# REV1.net
KiCad netlist of a schematic drawn in EAGLE
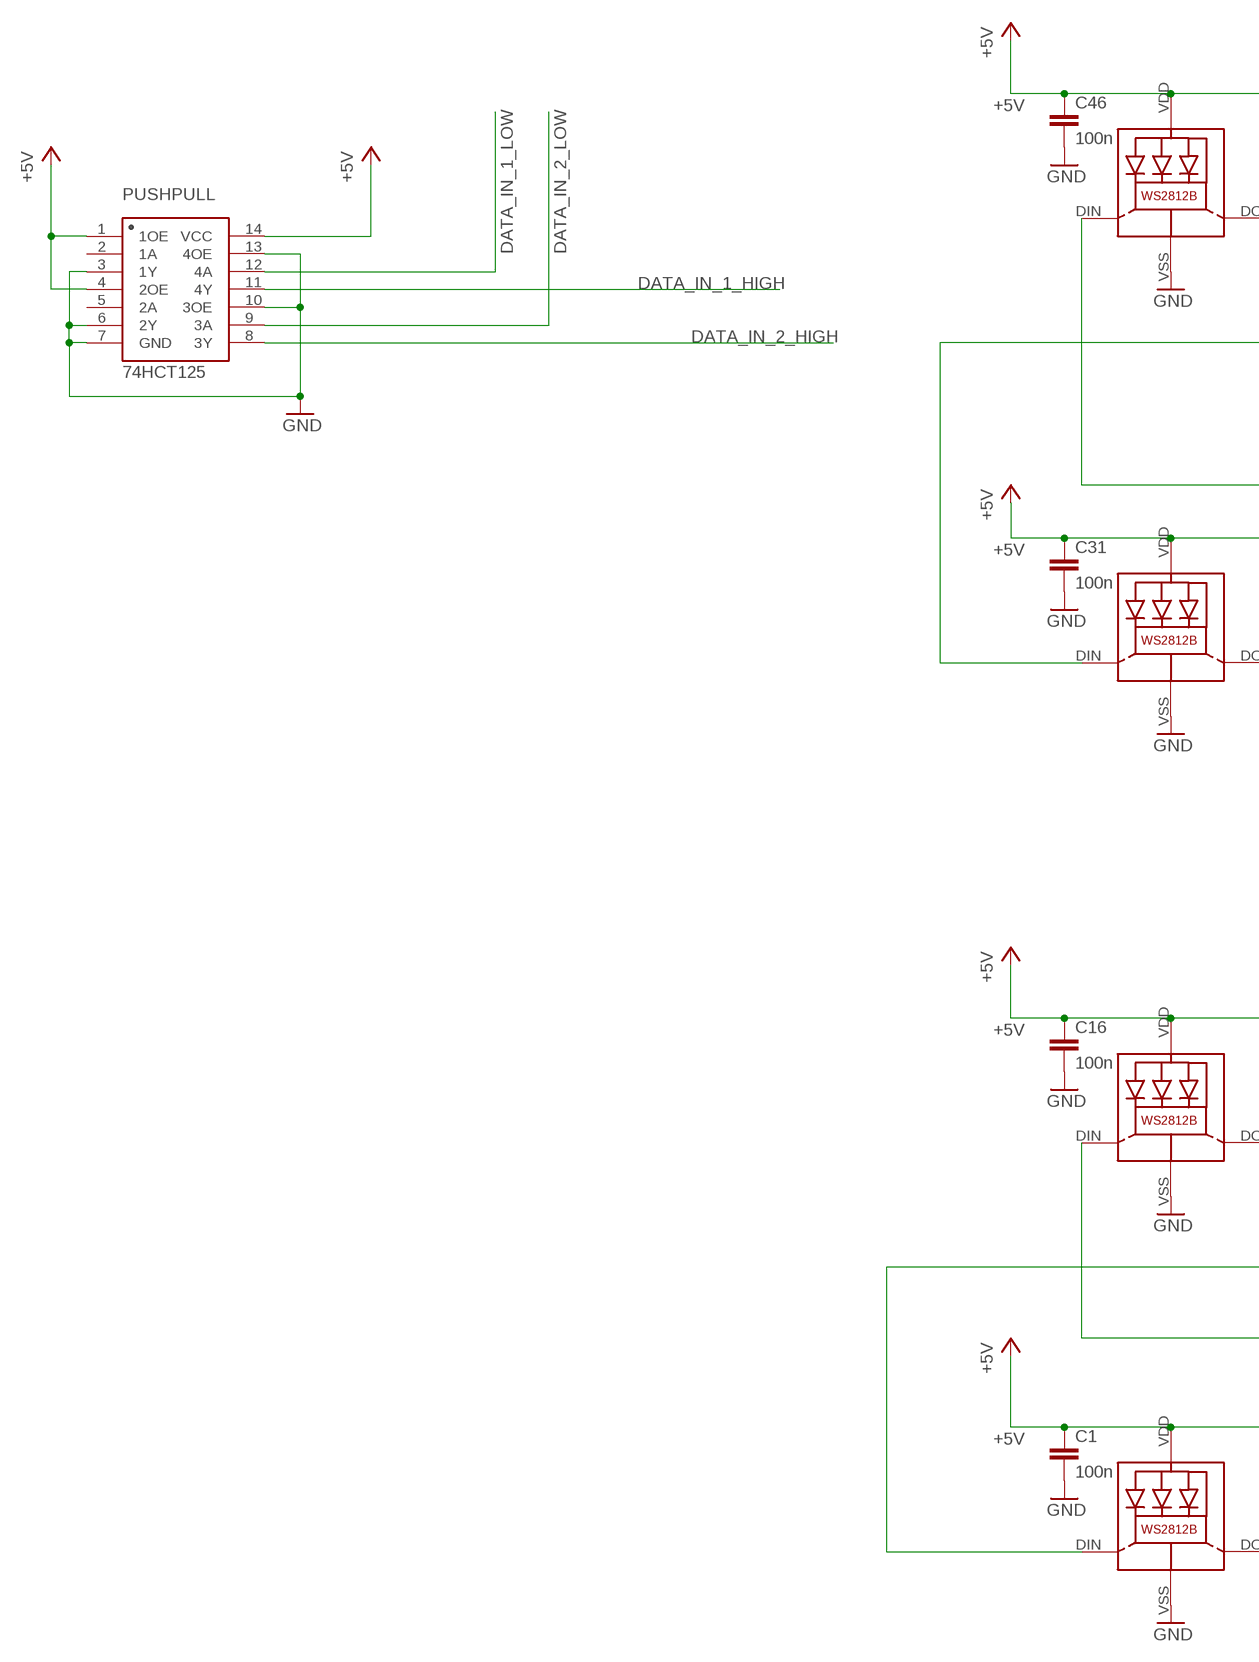
[diagram p0: schematic, sheet 1, part 1 of 2]
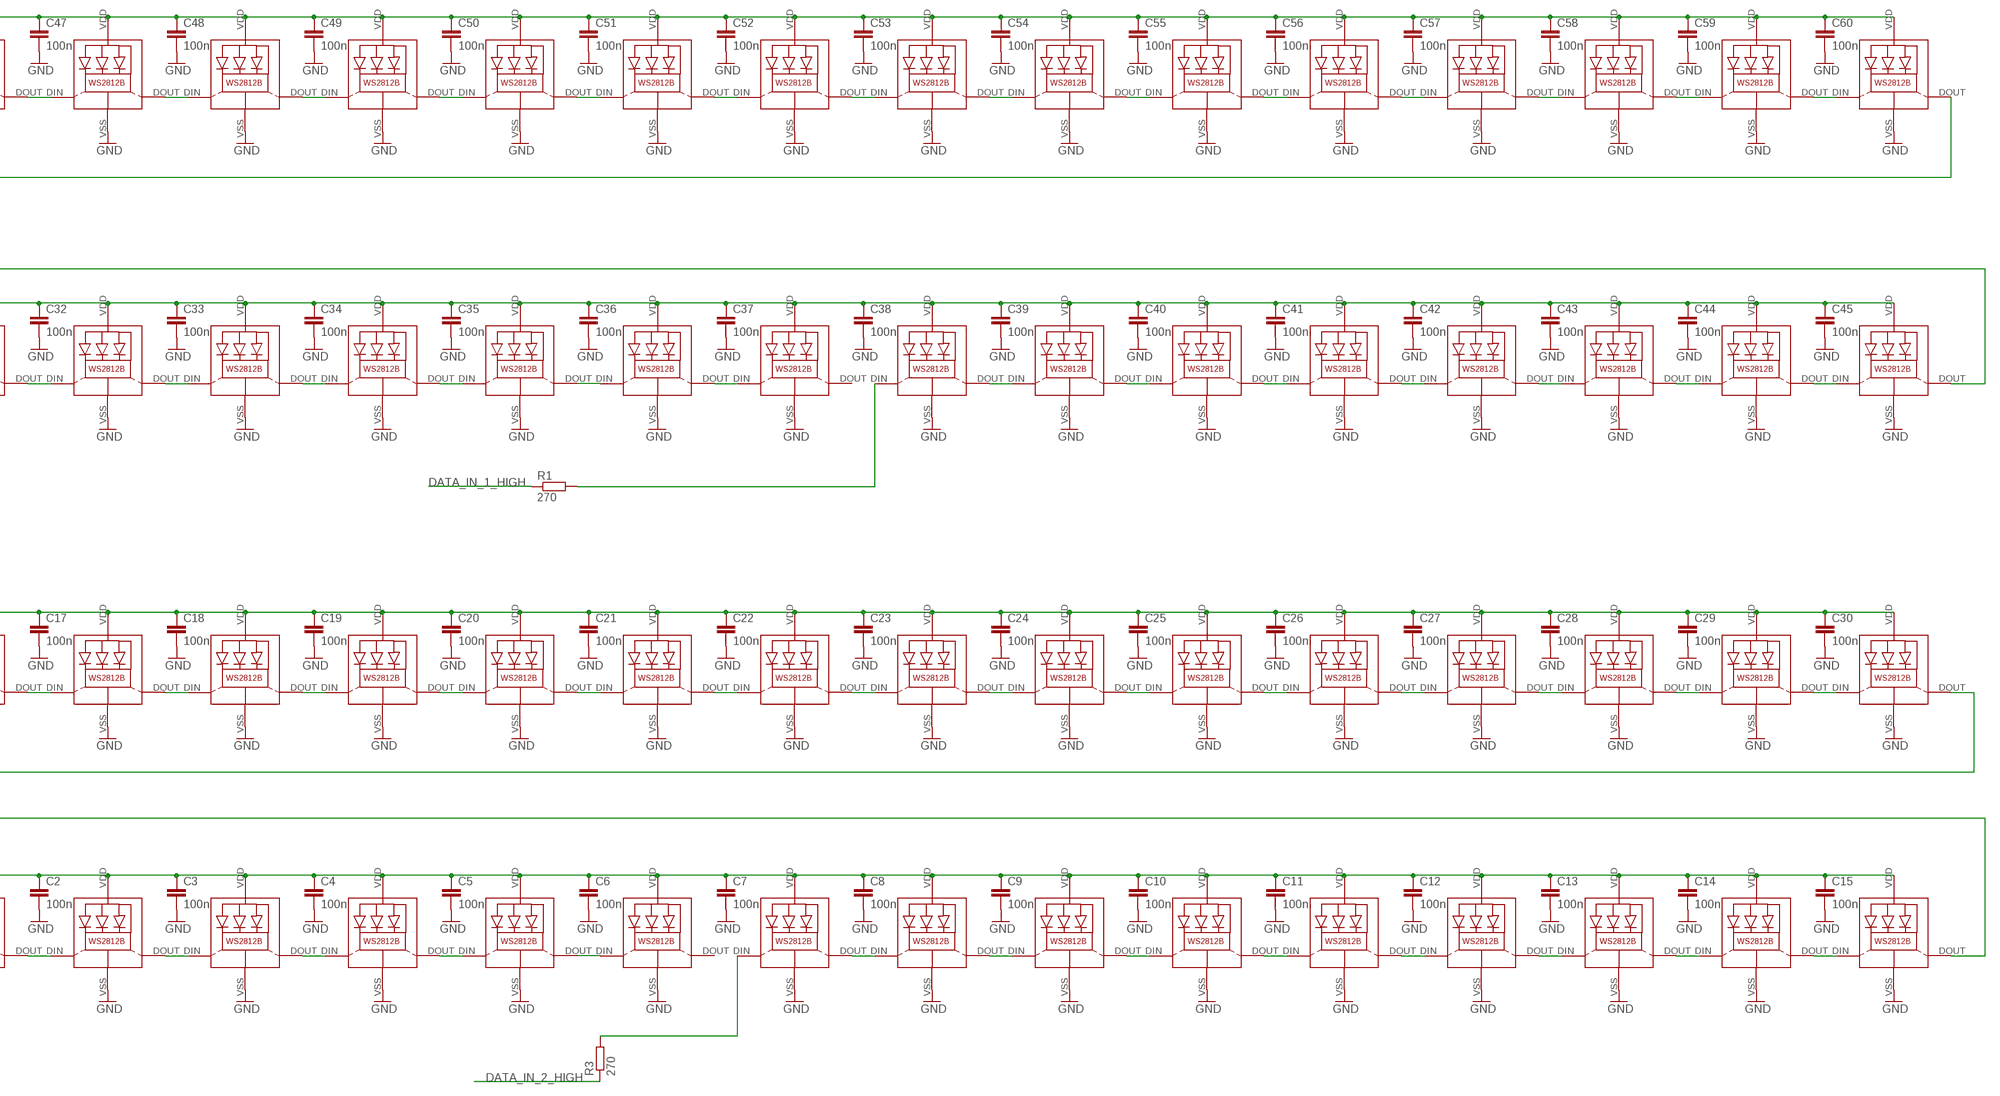
[diagram p1: schematic, sheet 1, part 2 of 2]
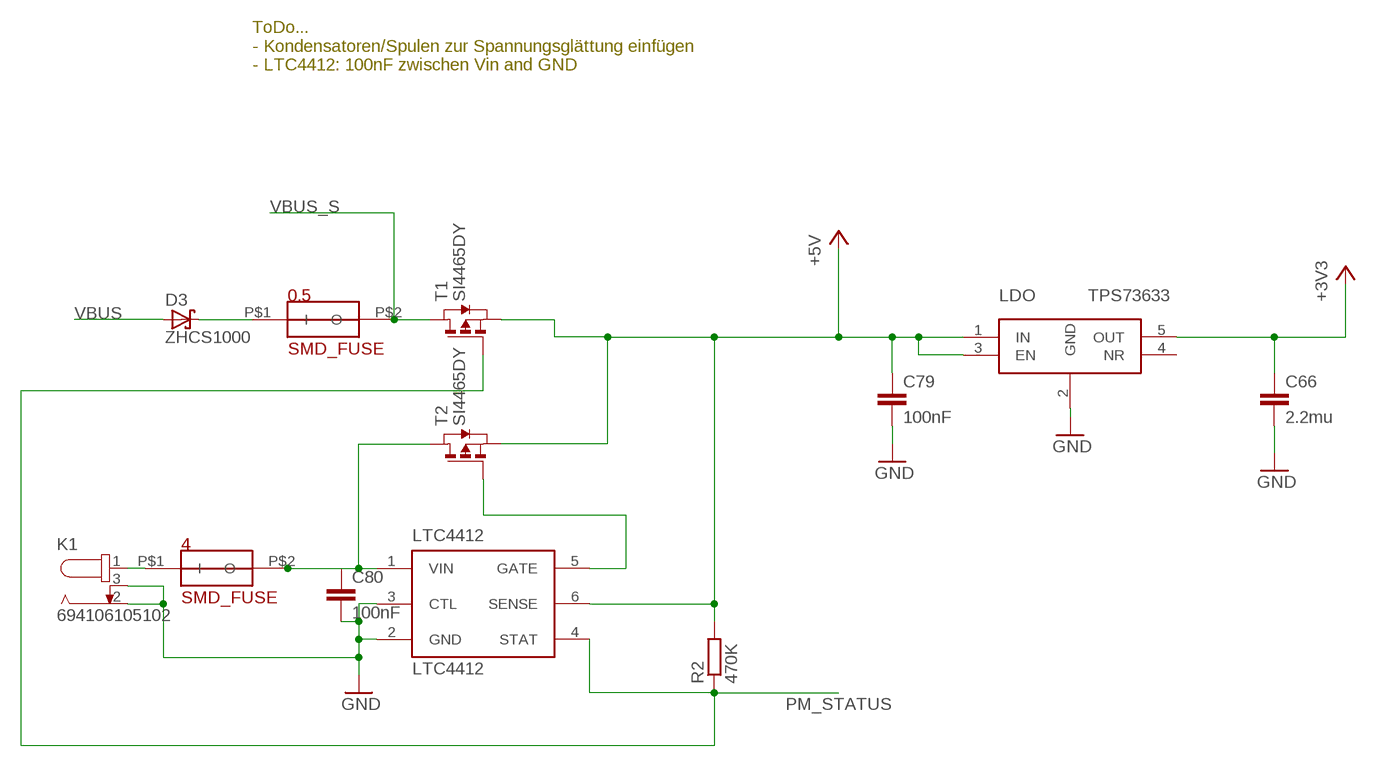
[diagram p2: schematic, sheet 2]
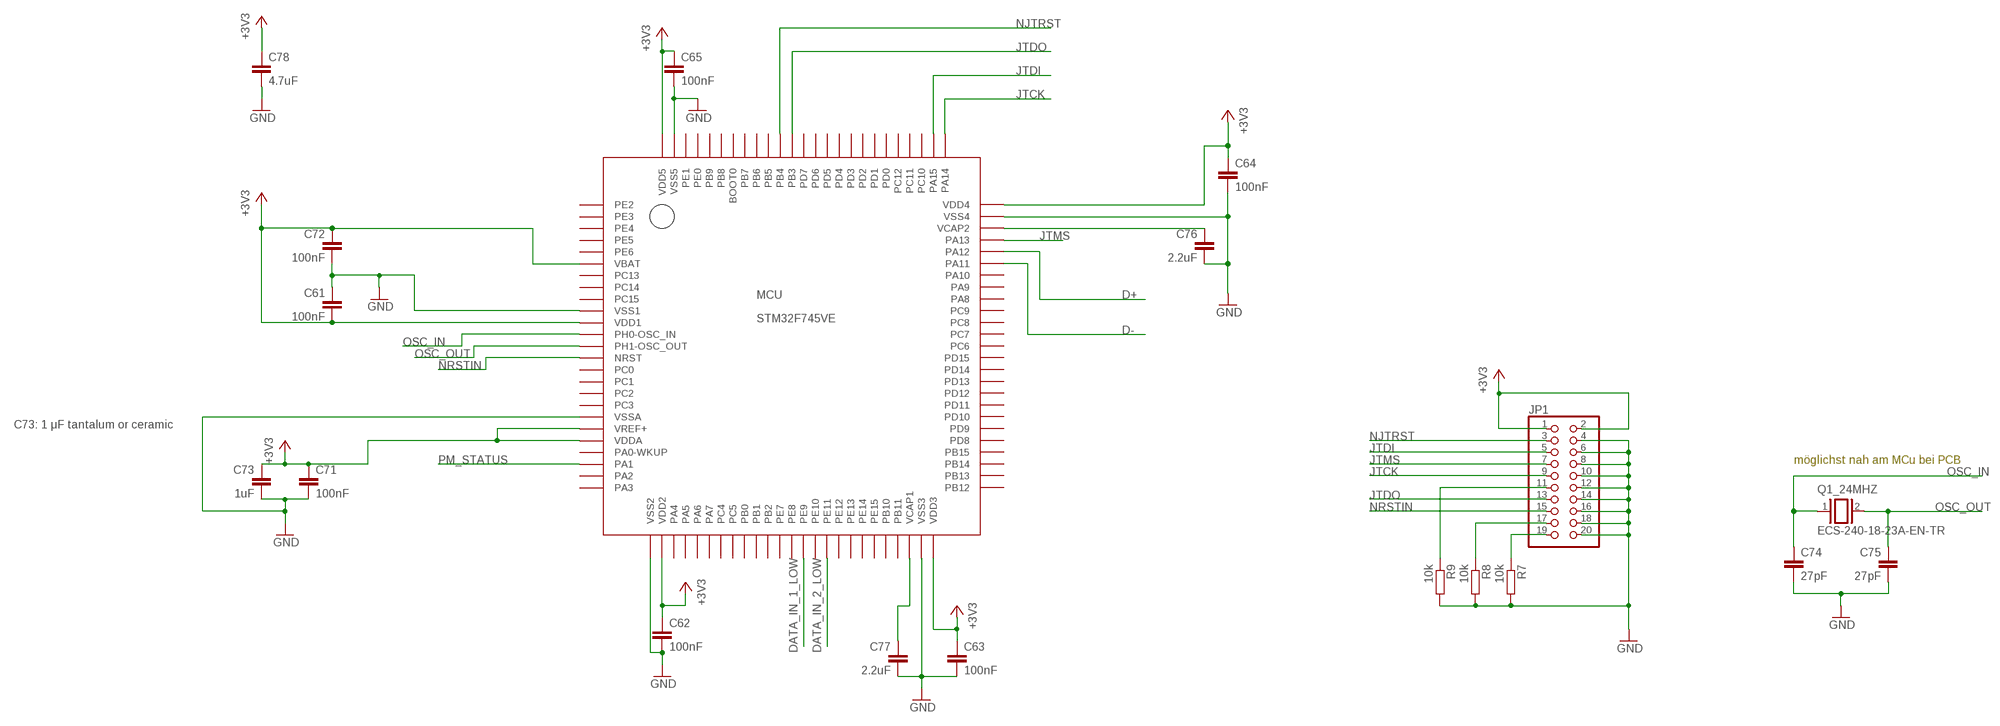
[diagram p3: schematic, sheet 3]
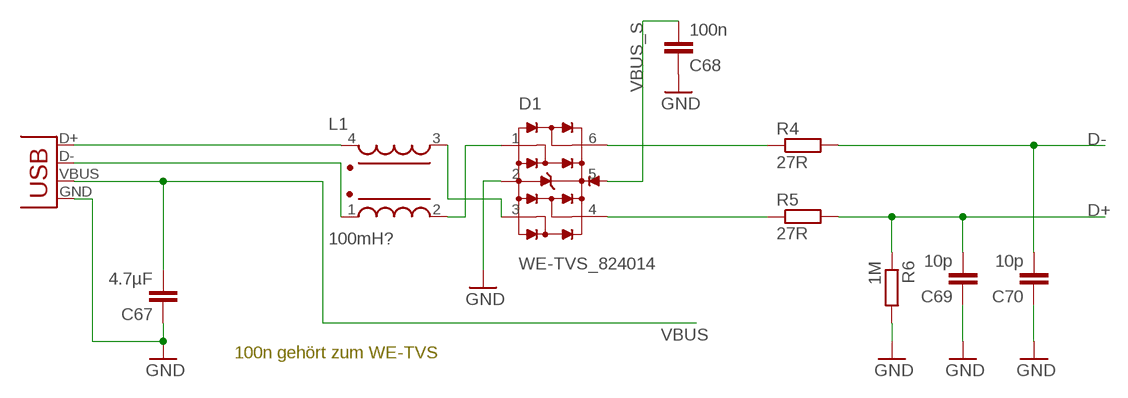
[diagram p4: schematic, sheet 4]

(export (version "E")
  (design (tool "Eeschema 10.0.6"))
  (components
    (comp (ref "C1")
      (value "100n")
      (footprint "eagle-import:C0603")
      (libsource (lib "eagle-import") (part "C-EUC0603"))
    )
    (comp (ref "C2")
      (value "100n")
      (footprint "eagle-import:C0603")
      (libsource (lib "eagle-import") (part "C-EUC0603"))
    )
    (comp (ref "C3")
      (value "100n")
      (footprint "eagle-import:C0603")
      (libsource (lib "eagle-import") (part "C-EUC0603"))
    )
    (comp (ref "C4")
      (value "100n")
      (footprint "eagle-import:C0603")
      (libsource (lib "eagle-import") (part "C-EUC0603"))
    )
    (comp (ref "C5")
      (value "100n")
      (footprint "eagle-import:C0603")
      (libsource (lib "eagle-import") (part "C-EUC0603"))
    )
    (comp (ref "C6")
      (value "100n")
      (footprint "eagle-import:C0603")
      (libsource (lib "eagle-import") (part "C-EUC0603"))
    )
    (comp (ref "C7")
      (value "100n")
      (footprint "eagle-import:C0603")
      (libsource (lib "eagle-import") (part "C-EUC0603"))
    )
    (comp (ref "C8")
      (value "100n")
      (footprint "eagle-import:C0603")
      (libsource (lib "eagle-import") (part "C-EUC0603"))
    )
    (comp (ref "C9")
      (value "100n")
      (footprint "eagle-import:C0603")
      (libsource (lib "eagle-import") (part "C-EUC0603"))
    )
    (comp (ref "C10")
      (value "100n")
      (footprint "eagle-import:C0603")
      (libsource (lib "eagle-import") (part "C-EUC0603"))
    )
    (comp (ref "C11")
      (value "100n")
      (footprint "eagle-import:C0603")
      (libsource (lib "eagle-import") (part "C-EUC0603"))
    )
    (comp (ref "C12")
      (value "100n")
      (footprint "eagle-import:C0603")
      (libsource (lib "eagle-import") (part "C-EUC0603"))
    )
    (comp (ref "C13")
      (value "100n")
      (footprint "eagle-import:C0603")
      (libsource (lib "eagle-import") (part "C-EUC0603"))
    )
    (comp (ref "C14")
      (value "100n")
      (footprint "eagle-import:C0603")
      (libsource (lib "eagle-import") (part "C-EUC0603"))
    )
    (comp (ref "C15")
      (value "100n")
      (footprint "eagle-import:C0603")
      (libsource (lib "eagle-import") (part "C-EUC0603"))
    )
    (comp (ref "C16")
      (value "100n")
      (footprint "eagle-import:C0603")
      (libsource (lib "eagle-import") (part "C-EUC0603"))
    )
    (comp (ref "C17")
      (value "100n")
      (footprint "eagle-import:C0603")
      (libsource (lib "eagle-import") (part "C-EUC0603"))
    )
    (comp (ref "C18")
      (value "100n")
      (footprint "eagle-import:C0603")
      (libsource (lib "eagle-import") (part "C-EUC0603"))
    )
    (comp (ref "C19")
      (value "100n")
      (footprint "eagle-import:C0603")
      (libsource (lib "eagle-import") (part "C-EUC0603"))
    )
    (comp (ref "C20")
      (value "100n")
      (footprint "eagle-import:C0603")
      (libsource (lib "eagle-import") (part "C-EUC0603"))
    )
    (comp (ref "C21")
      (value "100n")
      (footprint "eagle-import:C0603")
      (libsource (lib "eagle-import") (part "C-EUC0603"))
    )
    (comp (ref "C22")
      (value "100n")
      (footprint "eagle-import:C0603")
      (libsource (lib "eagle-import") (part "C-EUC0603"))
    )
    (comp (ref "C23")
      (value "100n")
      (footprint "eagle-import:C0603")
      (libsource (lib "eagle-import") (part "C-EUC0603"))
    )
    (comp (ref "C24")
      (value "100n")
      (footprint "eagle-import:C0603")
      (libsource (lib "eagle-import") (part "C-EUC0603"))
    )
    (comp (ref "C25")
      (value "100n")
      (footprint "eagle-import:C0603")
      (libsource (lib "eagle-import") (part "C-EUC0603"))
    )
    (comp (ref "C26")
      (value "100n")
      (footprint "eagle-import:C0603")
      (libsource (lib "eagle-import") (part "C-EUC0603"))
    )
    (comp (ref "C27")
      (value "100n")
      (footprint "eagle-import:C0603")
      (libsource (lib "eagle-import") (part "C-EUC0603"))
    )
    (comp (ref "C28")
      (value "100n")
      (footprint "eagle-import:C0603")
      (libsource (lib "eagle-import") (part "C-EUC0603"))
    )
    (comp (ref "C29")
      (value "100n")
      (footprint "eagle-import:C0603")
      (libsource (lib "eagle-import") (part "C-EUC0603"))
    )
    (comp (ref "C30")
      (value "100n")
      (footprint "eagle-import:C0603")
      (libsource (lib "eagle-import") (part "C-EUC0603"))
    )
    (comp (ref "C31")
      (value "100n")
      (footprint "eagle-import:C0603")
      (libsource (lib "eagle-import") (part "C-EUC0603"))
    )
    (comp (ref "C32")
      (value "100n")
      (footprint "eagle-import:C0603")
      (libsource (lib "eagle-import") (part "C-EUC0603"))
    )
    (comp (ref "C33")
      (value "100n")
      (footprint "eagle-import:C0603")
      (libsource (lib "eagle-import") (part "C-EUC0603"))
    )
    (comp (ref "C34")
      (value "100n")
      (footprint "eagle-import:C0603")
      (libsource (lib "eagle-import") (part "C-EUC0603"))
    )
    (comp (ref "C35")
      (value "100n")
      (footprint "eagle-import:C0603")
      (libsource (lib "eagle-import") (part "C-EUC0603"))
    )
    (comp (ref "C36")
      (value "100n")
      (footprint "eagle-import:C0603")
      (libsource (lib "eagle-import") (part "C-EUC0603"))
    )
    (comp (ref "C37")
      (value "100n")
      (footprint "eagle-import:C0603")
      (libsource (lib "eagle-import") (part "C-EUC0603"))
    )
    (comp (ref "C38")
      (value "100n")
      (footprint "eagle-import:C0603")
      (libsource (lib "eagle-import") (part "C-EUC0603"))
    )
    (comp (ref "C39")
      (value "100n")
      (footprint "eagle-import:C0603")
      (libsource (lib "eagle-import") (part "C-EUC0603"))
    )
    (comp (ref "C40")
      (value "100n")
      (footprint "eagle-import:C0603")
      (libsource (lib "eagle-import") (part "C-EUC0603"))
    )
    (comp (ref "C41")
      (value "100n")
      (footprint "eagle-import:C0603")
      (libsource (lib "eagle-import") (part "C-EUC0603"))
    )
    (comp (ref "C42")
      (value "100n")
      (footprint "eagle-import:C0603")
      (libsource (lib "eagle-import") (part "C-EUC0603"))
    )
    (comp (ref "C43")
      (value "100n")
      (footprint "eagle-import:C0603")
      (libsource (lib "eagle-import") (part "C-EUC0603"))
    )
    (comp (ref "C44")
      (value "100n")
      (footprint "eagle-import:C0603")
      (libsource (lib "eagle-import") (part "C-EUC0603"))
    )
    (comp (ref "C45")
      (value "100n")
      (footprint "eagle-import:C0603")
      (libsource (lib "eagle-import") (part "C-EUC0603"))
    )
    (comp (ref "C46")
      (value "100n")
      (footprint "eagle-import:C0603")
      (libsource (lib "eagle-import") (part "C-EUC0603"))
    )
    (comp (ref "C47")
      (value "100n")
      (footprint "eagle-import:C0603")
      (libsource (lib "eagle-import") (part "C-EUC0603"))
    )
    (comp (ref "C48")
      (value "100n")
      (footprint "eagle-import:C0603")
      (libsource (lib "eagle-import") (part "C-EUC0603"))
    )
    (comp (ref "C49")
      (value "100n")
      (footprint "eagle-import:C0603")
      (libsource (lib "eagle-import") (part "C-EUC0603"))
    )
    (comp (ref "C50")
      (value "100n")
      (footprint "eagle-import:C0603")
      (libsource (lib "eagle-import") (part "C-EUC0603"))
    )
    (comp (ref "C51")
      (value "100n")
      (footprint "eagle-import:C0603")
      (libsource (lib "eagle-import") (part "C-EUC0603"))
    )
    (comp (ref "C52")
      (value "100n")
      (footprint "eagle-import:C0603")
      (libsource (lib "eagle-import") (part "C-EUC0603"))
    )
    (comp (ref "C53")
      (value "100n")
      (footprint "eagle-import:C0603")
      (libsource (lib "eagle-import") (part "C-EUC0603"))
    )
    (comp (ref "C54")
      (value "100n")
      (footprint "eagle-import:C0603")
      (libsource (lib "eagle-import") (part "C-EUC0603"))
    )
    (comp (ref "C55")
      (value "100n")
      (footprint "eagle-import:C0603")
      (libsource (lib "eagle-import") (part "C-EUC0603"))
    )
    (comp (ref "C56")
      (value "100n")
      (footprint "eagle-import:C0603")
      (libsource (lib "eagle-import") (part "C-EUC0603"))
    )
    (comp (ref "C57")
      (value "100n")
      (footprint "eagle-import:C0603")
      (libsource (lib "eagle-import") (part "C-EUC0603"))
    )
    (comp (ref "C58")
      (value "100n")
      (footprint "eagle-import:C0603")
      (libsource (lib "eagle-import") (part "C-EUC0603"))
    )
    (comp (ref "C59")
      (value "100n")
      (footprint "eagle-import:C0603")
      (libsource (lib "eagle-import") (part "C-EUC0603"))
    )
    (comp (ref "C60")
      (value "100n")
      (footprint "eagle-import:C0603")
      (libsource (lib "eagle-import") (part "C-EUC0603"))
    )
    (comp (ref "LED1")
      (value "WS2812B")
      (footprint "eagle-import:WS2812B")
      (libsource (lib "eagle-import") (part "WS2812B"))
    )
    (comp (ref "LED2")
      (value "WS2812B")
      (footprint "eagle-import:WS2812B")
      (libsource (lib "eagle-import") (part "WS2812B"))
    )
    (comp (ref "LED3")
      (value "WS2812B")
      (footprint "eagle-import:WS2812B")
      (libsource (lib "eagle-import") (part "WS2812B"))
    )
    (comp (ref "LED4")
      (value "WS2812B")
      (footprint "eagle-import:WS2812B")
      (libsource (lib "eagle-import") (part "WS2812B"))
    )
    (comp (ref "LED5")
      (value "WS2812B")
      (footprint "eagle-import:WS2812B")
      (libsource (lib "eagle-import") (part "WS2812B"))
    )
    (comp (ref "LED6")
      (value "WS2812B")
      (footprint "eagle-import:WS2812B")
      (libsource (lib "eagle-import") (part "WS2812B"))
    )
    (comp (ref "LED7")
      (value "WS2812B")
      (footprint "eagle-import:WS2812B")
      (libsource (lib "eagle-import") (part "WS2812B"))
    )
    (comp (ref "LED8")
      (value "WS2812B")
      (footprint "eagle-import:WS2812B")
      (libsource (lib "eagle-import") (part "WS2812B"))
    )
    (comp (ref "LED9")
      (value "WS2812B")
      (footprint "eagle-import:WS2812B")
      (libsource (lib "eagle-import") (part "WS2812B"))
    )
    (comp (ref "LED10")
      (value "WS2812B")
      (footprint "eagle-import:WS2812B")
      (libsource (lib "eagle-import") (part "WS2812B"))
    )
    (comp (ref "LED11")
      (value "WS2812B")
      (footprint "eagle-import:WS2812B")
      (libsource (lib "eagle-import") (part "WS2812B"))
    )
    (comp (ref "LED12")
      (value "WS2812B")
      (footprint "eagle-import:WS2812B")
      (libsource (lib "eagle-import") (part "WS2812B"))
    )
    (comp (ref "LED13")
      (value "WS2812B")
      (footprint "eagle-import:WS2812B")
      (libsource (lib "eagle-import") (part "WS2812B"))
    )
    (comp (ref "LED14")
      (value "WS2812B")
      (footprint "eagle-import:WS2812B")
      (libsource (lib "eagle-import") (part "WS2812B"))
    )
    (comp (ref "LED15")
      (value "WS2812B")
      (footprint "eagle-import:WS2812B")
      (libsource (lib "eagle-import") (part "WS2812B"))
    )
    (comp (ref "LED16")
      (value "WS2812B")
      (footprint "eagle-import:WS2812B")
      (libsource (lib "eagle-import") (part "WS2812B"))
    )
    (comp (ref "LED17")
      (value "WS2812B")
      (footprint "eagle-import:WS2812B")
      (libsource (lib "eagle-import") (part "WS2812B"))
    )
    (comp (ref "LED18")
      (value "WS2812B")
      (footprint "eagle-import:WS2812B")
      (libsource (lib "eagle-import") (part "WS2812B"))
    )
    (comp (ref "LED19")
      (value "WS2812B")
      (footprint "eagle-import:WS2812B")
      (libsource (lib "eagle-import") (part "WS2812B"))
    )
    (comp (ref "LED20")
      (value "WS2812B")
      (footprint "eagle-import:WS2812B")
      (libsource (lib "eagle-import") (part "WS2812B"))
    )
    (comp (ref "LED21")
      (value "WS2812B")
      (footprint "eagle-import:WS2812B")
      (libsource (lib "eagle-import") (part "WS2812B"))
    )
    (comp (ref "LED22")
      (value "WS2812B")
      (footprint "eagle-import:WS2812B")
      (libsource (lib "eagle-import") (part "WS2812B"))
    )
    (comp (ref "LED23")
      (value "WS2812B")
      (footprint "eagle-import:WS2812B")
      (libsource (lib "eagle-import") (part "WS2812B"))
    )
    (comp (ref "LED24")
      (value "WS2812B")
      (footprint "eagle-import:WS2812B")
      (libsource (lib "eagle-import") (part "WS2812B"))
    )
    (comp (ref "LED25")
      (value "WS2812B")
      (footprint "eagle-import:WS2812B")
      (libsource (lib "eagle-import") (part "WS2812B"))
    )
    (comp (ref "LED26")
      (value "WS2812B")
      (footprint "eagle-import:WS2812B")
      (libsource (lib "eagle-import") (part "WS2812B"))
    )
    (comp (ref "LED27")
      (value "WS2812B")
      (footprint "eagle-import:WS2812B")
      (libsource (lib "eagle-import") (part "WS2812B"))
    )
    (comp (ref "LED28")
      (value "WS2812B")
      (footprint "eagle-import:WS2812B")
      (libsource (lib "eagle-import") (part "WS2812B"))
    )
    (comp (ref "LED29")
      (value "WS2812B")
      (footprint "eagle-import:WS2812B")
      (libsource (lib "eagle-import") (part "WS2812B"))
    )
    (comp (ref "LED30")
      (value "WS2812B")
      (footprint "eagle-import:WS2812B")
      (libsource (lib "eagle-import") (part "WS2812B"))
    )
    (comp (ref "LED31")
      (value "WS2812B")
      (footprint "eagle-import:WS2812B")
      (libsource (lib "eagle-import") (part "WS2812B"))
    )
    (comp (ref "LED32")
      (value "WS2812B")
      (footprint "eagle-import:WS2812B")
      (libsource (lib "eagle-import") (part "WS2812B"))
    )
    (comp (ref "LED33")
      (value "WS2812B")
      (footprint "eagle-import:WS2812B")
      (libsource (lib "eagle-import") (part "WS2812B"))
    )
    (comp (ref "LED34")
      (value "WS2812B")
      (footprint "eagle-import:WS2812B")
      (libsource (lib "eagle-import") (part "WS2812B"))
    )
    (comp (ref "LED35")
      (value "WS2812B")
      (footprint "eagle-import:WS2812B")
      (libsource (lib "eagle-import") (part "WS2812B"))
    )
    (comp (ref "LED36")
      (value "WS2812B")
      (footprint "eagle-import:WS2812B")
      (libsource (lib "eagle-import") (part "WS2812B"))
    )
    (comp (ref "LED37")
      (value "WS2812B")
      (footprint "eagle-import:WS2812B")
      (libsource (lib "eagle-import") (part "WS2812B"))
    )
    (comp (ref "LED38")
      (value "WS2812B")
      (footprint "eagle-import:WS2812B")
      (libsource (lib "eagle-import") (part "WS2812B"))
    )
    (comp (ref "LED39")
      (value "WS2812B")
      (footprint "eagle-import:WS2812B")
      (libsource (lib "eagle-import") (part "WS2812B"))
    )
    (comp (ref "LED40")
      (value "WS2812B")
      (footprint "eagle-import:WS2812B")
      (libsource (lib "eagle-import") (part "WS2812B"))
    )
    (comp (ref "LED41")
      (value "WS2812B")
      (footprint "eagle-import:WS2812B")
      (libsource (lib "eagle-import") (part "WS2812B"))
    )
    (comp (ref "LED42")
      (value "WS2812B")
      (footprint "eagle-import:WS2812B")
      (libsource (lib "eagle-import") (part "WS2812B"))
    )
    (comp (ref "LED43")
      (value "WS2812B")
      (footprint "eagle-import:WS2812B")
      (libsource (lib "eagle-import") (part "WS2812B"))
    )
    (comp (ref "LED44")
      (value "WS2812B")
      (footprint "eagle-import:WS2812B")
      (libsource (lib "eagle-import") (part "WS2812B"))
    )
    (comp (ref "LED45")
      (value "WS2812B")
      (footprint "eagle-import:WS2812B")
      (libsource (lib "eagle-import") (part "WS2812B"))
    )
    (comp (ref "LED46")
      (value "WS2812B")
      (footprint "eagle-import:WS2812B")
      (libsource (lib "eagle-import") (part "WS2812B"))
    )
    (comp (ref "LED47")
      (value "WS2812B")
      (footprint "eagle-import:WS2812B")
      (libsource (lib "eagle-import") (part "WS2812B"))
    )
    (comp (ref "LED48")
      (value "WS2812B")
      (footprint "eagle-import:WS2812B")
      (libsource (lib "eagle-import") (part "WS2812B"))
    )
    (comp (ref "LED49")
      (value "WS2812B")
      (footprint "eagle-import:WS2812B")
      (libsource (lib "eagle-import") (part "WS2812B"))
    )
    (comp (ref "LED50")
      (value "WS2812B")
      (footprint "eagle-import:WS2812B")
      (libsource (lib "eagle-import") (part "WS2812B"))
    )
    (comp (ref "LED51")
      (value "WS2812B")
      (footprint "eagle-import:WS2812B")
      (libsource (lib "eagle-import") (part "WS2812B"))
    )
    (comp (ref "LED52")
      (value "WS2812B")
      (footprint "eagle-import:WS2812B")
      (libsource (lib "eagle-import") (part "WS2812B"))
    )
    (comp (ref "LED53")
      (value "WS2812B")
      (footprint "eagle-import:WS2812B")
      (libsource (lib "eagle-import") (part "WS2812B"))
    )
    (comp (ref "LED54")
      (value "WS2812B")
      (footprint "eagle-import:WS2812B")
      (libsource (lib "eagle-import") (part "WS2812B"))
    )
    (comp (ref "LED55")
      (value "WS2812B")
      (footprint "eagle-import:WS2812B")
      (libsource (lib "eagle-import") (part "WS2812B"))
    )
    (comp (ref "LED56")
      (value "WS2812B")
      (footprint "eagle-import:WS2812B")
      (libsource (lib "eagle-import") (part "WS2812B"))
    )
    (comp (ref "LED57")
      (value "WS2812B")
      (footprint "eagle-import:WS2812B")
      (libsource (lib "eagle-import") (part "WS2812B"))
    )
    (comp (ref "LED58")
      (value "WS2812B")
      (footprint "eagle-import:WS2812B")
      (libsource (lib "eagle-import") (part "WS2812B"))
    )
    (comp (ref "LED59")
      (value "WS2812B")
      (footprint "eagle-import:WS2812B")
      (libsource (lib "eagle-import") (part "WS2812B"))
    )
    (comp (ref "LED60")
      (value "WS2812B")
      (footprint "eagle-import:WS2812B")
      (libsource (lib "eagle-import") (part "WS2812B"))
    )
    (comp (ref "PUSHPULL")
      (value "74HCT125")
      (footprint "eagle-import:SO-14DW")
      (libsource (lib "eagle-import") (part "74HCT125"))
    )
    (comp (ref "R1")
      (value "270")
      (footprint "eagle-import:R0603")
      (libsource (lib "eagle-import") (part "R-EU_R0603"))
    )
    (comp (ref "R3")
      (value "270")
      (footprint "eagle-import:R0603")
      (libsource (lib "eagle-import") (part "R-EU_R0603"))
    )
    (comp (ref "C67")
      (value "4.7µF")
      (footprint "eagle-import:C0603")
      (libsource (lib "eagle-import") (part "C-EUC0603"))
    )
    (comp (ref "C68")
      (value "100n")
      (footprint "eagle-import:C0603")
      (libsource (lib "eagle-import") (part "C-EUC0603"))
    )
    (comp (ref "C69")
      (value "10p")
      (footprint "eagle-import:C0603")
      (libsource (lib "eagle-import") (part "C-EUC0603"))
    )
    (comp (ref "C70")
      (value "10p")
      (footprint "eagle-import:C0603")
      (libsource (lib "eagle-import") (part "C-EUC0603"))
    )
    (comp (ref "D1")
      (value "WE-TVS_824014")
      (footprint "eagle-import:WE-TVS_SOT23-6L")
      (libsource (lib "eagle-import") (part "WE-TVS_824014"))
    )
    (comp (ref "L1")
      (value "100mH?")
      (footprint "eagle-import:WE-CNSW_0805")
      (libsource (lib "eagle-import") (part "WE-CNSW_0805"))
    )
    (comp (ref "R4")
      (value "27R")
      (footprint "eagle-import:R0603")
      (libsource (lib "eagle-import") (part "R-EU_R0603"))
    )
    (comp (ref "R5")
      (value "27R")
      (footprint "eagle-import:R0603")
      (libsource (lib "eagle-import") (part "R-EU_R0603"))
    )
    (comp (ref "R6")
      (value "1M")
      (footprint "eagle-import:R0603")
      (libsource (lib "eagle-import") (part "R-EU_R0603"))
    )
    (comp (ref "X1")
      (value "USBSMD")
      (footprint "eagle-import:USB-MINIB")
      (libsource (lib "eagle-import") (part "USBSMD"))
    )
    (comp (ref "0.5")
      (value "SMD_FUSE")
      (footprint "eagle-import:FUSE")
      (libsource (lib "eagle-import") (part "SMD_FUSE"))
    )
    (comp (ref "4")
      (value "SMD_FUSE")
      (footprint "eagle-import:FUSE")
      (libsource (lib "eagle-import") (part "SMD_FUSE"))
    )
    (comp (ref "C66")
      (value "2.2mu")
      (footprint "eagle-import:C0603")
      (libsource (lib "eagle-import") (part "C-EUC0603"))
    )
    (comp (ref "C79")
      (value "100nF")
      (footprint "eagle-import:C0603")
      (libsource (lib "eagle-import") (part "C-EUC0603"))
    )
    (comp (ref "C80")
      (value "100nF")
      (footprint "eagle-import:C0603")
      (libsource (lib "eagle-import") (part "C-EUC0603"))
    )
    (comp (ref "D3")
      (value "ZHCS1000")
      (footprint "eagle-import:SOT23")
      (libsource (lib "eagle-import") (part "ZHCS1000"))
    )
    (comp (ref "K1")
      (value "694106105102")
      (footprint "eagle-import:694106105102")
      (libsource (lib "eagle-import") (part "694106105102"))
    )
    (comp (ref "LDO")
      (value "TPS73633")
      (footprint "eagle-import:SOT23-DBV")
      (libsource (lib "eagle-import") (part "TPS73633"))
    )
    (comp (ref "LTC4412")
      (value "LTC4412")
      (footprint "eagle-import:SOT23-6L")
      (libsource (lib "eagle-import") (part "LTC4412"))
    )
    (comp (ref "R2")
      (value "470K")
      (footprint "eagle-import:R0603")
      (libsource (lib "eagle-import") (part "R-EU_R0603"))
    )
    (comp (ref "T1")
      (value "SI4465DY")
      (footprint "eagle-import:SO08")
      (libsource (lib "eagle-import") (part "PMOSSOT223SO8"))
    )
    (comp (ref "T2")
      (value "SI4465DY")
      (footprint "eagle-import:SO08")
      (libsource (lib "eagle-import") (part "PMOSSOT223SO8"))
    )
    (comp (ref "C61")
      (value "100nF")
      (footprint "eagle-import:C0603")
      (libsource (lib "eagle-import") (part "C-EUC0603"))
    )
    (comp (ref "C62")
      (value "100nF")
      (footprint "eagle-import:C0603")
      (libsource (lib "eagle-import") (part "C-EUC0603"))
    )
    (comp (ref "C63")
      (value "100nF")
      (footprint "eagle-import:C0603")
      (libsource (lib "eagle-import") (part "C-EUC0603"))
    )
    (comp (ref "C64")
      (value "100nF")
      (footprint "eagle-import:C0603")
      (libsource (lib "eagle-import") (part "C-EUC0603"))
    )
    (comp (ref "C65")
      (value "100nF")
      (footprint "eagle-import:C0603")
      (libsource (lib "eagle-import") (part "C-EUC0603"))
    )
    (comp (ref "C71")
      (value "100nF")
      (footprint "eagle-import:C0603")
      (libsource (lib "eagle-import") (part "C-EUC0603"))
    )
    (comp (ref "C72")
      (value "100nF")
      (footprint "eagle-import:C0603")
      (libsource (lib "eagle-import") (part "C-EUC0603"))
    )
    (comp (ref "C73")
      (value "1uF")
      (footprint "eagle-import:C0603")
      (libsource (lib "eagle-import") (part "C-EUC0603"))
    )
    (comp (ref "C74")
      (value "27pF")
      (footprint "eagle-import:C0603")
      (libsource (lib "eagle-import") (part "C-EUC0603"))
    )
    (comp (ref "C75")
      (value "27pF")
      (footprint "eagle-import:C0603")
      (libsource (lib "eagle-import") (part "C-EUC0603"))
    )
    (comp (ref "C76")
      (value "2.2uF")
      (footprint "eagle-import:C0603")
      (libsource (lib "eagle-import") (part "C-EUC0603"))
    )
    (comp (ref "C77")
      (value "2.2uF")
      (footprint "eagle-import:C0603")
      (libsource (lib "eagle-import") (part "C-EUC0603"))
    )
    (comp (ref "C78")
      (value "4.7uF")
      (footprint "eagle-import:C0603")
      (libsource (lib "eagle-import") (part "C-EUC0603"))
    )
    (comp (ref "JP1")
      (value "PINHD-2X10_2.54-SMD")
      (footprint "eagle-import:2X10SMD")
      (libsource (lib "eagle-import") (part "PINHD-2X10_2.54-SMD"))
    )
    (comp (ref "MCU")
      (value "STM32F745VE")
      (footprint "eagle-import:LQFP100")
      (libsource (lib "eagle-import") (part "STM32F745VE"))
    )
    (comp (ref "Q1_24MHZ")
      (value "ECS-240-18-23A-EN-TR")
      (footprint "eagle-import:ESC64A")
      (libsource (lib "eagle-import") (part "ECX64A"))
    )
    (comp (ref "R7")
      (value "10k")
      (footprint "eagle-import:R0603")
      (libsource (lib "eagle-import") (part "R-EU_R0603"))
    )
    (comp (ref "R8")
      (value "10k")
      (footprint "eagle-import:R0603")
      (libsource (lib "eagle-import") (part "R-EU_R0603"))
    )
    (comp (ref "R9")
      (value "10k")
      (footprint "eagle-import:R0603")
      (libsource (lib "eagle-import") (part "R-EU_R0603"))
    )
  )
  (nets
    (net (code "1") (name "+3V3") (class "Default")
      (node (ref "C61") (pin "2") (pinfunction "2_2") (pintype "passive"))
      (node (ref "C62") (pin "1") (pinfunction "1_1") (pintype "passive"))
      (node (ref "C63") (pin "1") (pinfunction "1_1") (pintype "passive"))
      (node (ref "C64") (pin "1") (pinfunction "1_1") (pintype "passive"))
      (node (ref "C65") (pin "1") (pinfunction "1_1") (pintype "passive"))
      (node (ref "C66") (pin "1") (pinfunction "1_1") (pintype "passive"))
      (node (ref "C71") (pin "1") (pinfunction "1_1") (pintype "passive"))
      (node (ref "C72") (pin "1") (pinfunction "1_1") (pintype "passive"))
      (node (ref "C73") (pin "1") (pinfunction "1_1") (pintype "passive"))
      (node (ref "C78") (pin "1") (pinfunction "1_1") (pintype "passive"))
      (node (ref "JP1") (pin "1") (pinfunction "1_1") (pintype "passive"))
      (node (ref "JP1") (pin "2") (pinfunction "2_2") (pintype "passive"))
      (node (ref "LDO") (pin "5") (pinfunction "OUT_5") (pintype "bidirectional"))
      (node (ref "MCU") (pin "100") (pinfunction "VDD5_100") (pintype "power_in"))
      (node (ref "MCU") (pin "11") (pinfunction "VDD1_11") (pintype "power_in"))
      (node (ref "MCU") (pin "20") (pinfunction "VREF+_20") (pintype "power_in"))
      (node (ref "MCU") (pin "21") (pinfunction "VDDA_21") (pintype "power_in"))
      (node (ref "MCU") (pin "27") (pinfunction "VDD2_27") (pintype "power_in"))
      (node (ref "MCU") (pin "50") (pinfunction "VDD3_50") (pintype "power_in"))
      (node (ref "MCU") (pin "6") (pinfunction "VBAT_6") (pintype "power_in"))
      (node (ref "MCU") (pin "75") (pinfunction "VDD4_75") (pintype "power_in"))
    )
    (net (code "2") (name "+5V") (class "Default")
      (node (ref "C1") (pin "1") (pinfunction "1_1") (pintype "passive"))
      (node (ref "C10") (pin "1") (pinfunction "1_1") (pintype "passive"))
      (node (ref "C11") (pin "1") (pinfunction "1_1") (pintype "passive"))
      (node (ref "C12") (pin "1") (pinfunction "1_1") (pintype "passive"))
      (node (ref "C13") (pin "1") (pinfunction "1_1") (pintype "passive"))
      (node (ref "C14") (pin "1") (pinfunction "1_1") (pintype "passive"))
      (node (ref "C15") (pin "1") (pinfunction "1_1") (pintype "passive"))
      (node (ref "C16") (pin "1") (pinfunction "1_1") (pintype "passive"))
      (node (ref "C17") (pin "1") (pinfunction "1_1") (pintype "passive"))
      (node (ref "C18") (pin "1") (pinfunction "1_1") (pintype "passive"))
      (node (ref "C19") (pin "1") (pinfunction "1_1") (pintype "passive"))
      (node (ref "C2") (pin "1") (pinfunction "1_1") (pintype "passive"))
      (node (ref "C20") (pin "1") (pinfunction "1_1") (pintype "passive"))
      (node (ref "C21") (pin "1") (pinfunction "1_1") (pintype "passive"))
      (node (ref "C22") (pin "1") (pinfunction "1_1") (pintype "passive"))
      (node (ref "C23") (pin "1") (pinfunction "1_1") (pintype "passive"))
      (node (ref "C24") (pin "1") (pinfunction "1_1") (pintype "passive"))
      (node (ref "C25") (pin "1") (pinfunction "1_1") (pintype "passive"))
      (node (ref "C26") (pin "1") (pinfunction "1_1") (pintype "passive"))
      (node (ref "C27") (pin "1") (pinfunction "1_1") (pintype "passive"))
      (node (ref "C28") (pin "1") (pinfunction "1_1") (pintype "passive"))
      (node (ref "C29") (pin "1") (pinfunction "1_1") (pintype "passive"))
      (node (ref "C3") (pin "1") (pinfunction "1_1") (pintype "passive"))
      (node (ref "C30") (pin "1") (pinfunction "1_1") (pintype "passive"))
      (node (ref "C31") (pin "1") (pinfunction "1_1") (pintype "passive"))
      (node (ref "C32") (pin "1") (pinfunction "1_1") (pintype "passive"))
      (node (ref "C33") (pin "1") (pinfunction "1_1") (pintype "passive"))
      (node (ref "C34") (pin "1") (pinfunction "1_1") (pintype "passive"))
      (node (ref "C35") (pin "1") (pinfunction "1_1") (pintype "passive"))
      (node (ref "C36") (pin "1") (pinfunction "1_1") (pintype "passive"))
      (node (ref "C37") (pin "1") (pinfunction "1_1") (pintype "passive"))
      (node (ref "C38") (pin "1") (pinfunction "1_1") (pintype "passive"))
      (node (ref "C39") (pin "1") (pinfunction "1_1") (pintype "passive"))
      (node (ref "C4") (pin "1") (pinfunction "1_1") (pintype "passive"))
      (node (ref "C40") (pin "1") (pinfunction "1_1") (pintype "passive"))
      (node (ref "C41") (pin "1") (pinfunction "1_1") (pintype "passive"))
      (node (ref "C42") (pin "1") (pinfunction "1_1") (pintype "passive"))
      (node (ref "C43") (pin "1") (pinfunction "1_1") (pintype "passive"))
      (node (ref "C44") (pin "1") (pinfunction "1_1") (pintype "passive"))
      (node (ref "C45") (pin "1") (pinfunction "1_1") (pintype "passive"))
      (node (ref "C46") (pin "1") (pinfunction "1_1") (pintype "passive"))
      (node (ref "C47") (pin "1") (pinfunction "1_1") (pintype "passive"))
      (node (ref "C48") (pin "1") (pinfunction "1_1") (pintype "passive"))
      (node (ref "C49") (pin "1") (pinfunction "1_1") (pintype "passive"))
      (node (ref "C5") (pin "1") (pinfunction "1_1") (pintype "passive"))
      (node (ref "C50") (pin "1") (pinfunction "1_1") (pintype "passive"))
      (node (ref "C51") (pin "1") (pinfunction "1_1") (pintype "passive"))
      (node (ref "C52") (pin "1") (pinfunction "1_1") (pintype "passive"))
      (node (ref "C53") (pin "1") (pinfunction "1_1") (pintype "passive"))
      (node (ref "C54") (pin "1") (pinfunction "1_1") (pintype "passive"))
      (node (ref "C55") (pin "1") (pinfunction "1_1") (pintype "passive"))
      (node (ref "C56") (pin "1") (pinfunction "1_1") (pintype "passive"))
      (node (ref "C57") (pin "1") (pinfunction "1_1") (pintype "passive"))
      (node (ref "C58") (pin "1") (pinfunction "1_1") (pintype "passive"))
      (node (ref "C59") (pin "1") (pinfunction "1_1") (pintype "passive"))
      (node (ref "C6") (pin "1") (pinfunction "1_1") (pintype "passive"))
      (node (ref "C60") (pin "1") (pinfunction "1_1") (pintype "passive"))
      (node (ref "C7") (pin "1") (pinfunction "1_1") (pintype "passive"))
      (node (ref "C79") (pin "1") (pinfunction "1_1") (pintype "passive"))
      (node (ref "C8") (pin "1") (pinfunction "1_1") (pintype "passive"))
      (node (ref "C9") (pin "1") (pinfunction "1_1") (pintype "passive"))
      (node (ref "LDO") (pin "1") (pinfunction "IN_1") (pintype "bidirectional"))
      (node (ref "LDO") (pin "3") (pinfunction "EN_3") (pintype "bidirectional"))
      (node (ref "LED1") (pin "VDD") (pinfunction "VDD_VDD") (pintype "power_in"))
      (node (ref "LED10") (pin "VDD") (pinfunction "VDD_VDD") (pintype "power_in"))
      (node (ref "LED11") (pin "VDD") (pinfunction "VDD_VDD") (pintype "power_in"))
      (node (ref "LED12") (pin "VDD") (pinfunction "VDD_VDD") (pintype "power_in"))
      (node (ref "LED13") (pin "VDD") (pinfunction "VDD_VDD") (pintype "power_in"))
      (node (ref "LED14") (pin "VDD") (pinfunction "VDD_VDD") (pintype "power_in"))
      (node (ref "LED15") (pin "VDD") (pinfunction "VDD_VDD") (pintype "power_in"))
      (node (ref "LED16") (pin "VDD") (pinfunction "VDD_VDD") (pintype "power_in"))
      (node (ref "LED17") (pin "VDD") (pinfunction "VDD_VDD") (pintype "power_in"))
      (node (ref "LED18") (pin "VDD") (pinfunction "VDD_VDD") (pintype "power_in"))
      (node (ref "LED19") (pin "VDD") (pinfunction "VDD_VDD") (pintype "power_in"))
      (node (ref "LED2") (pin "VDD") (pinfunction "VDD_VDD") (pintype "power_in"))
      (node (ref "LED20") (pin "VDD") (pinfunction "VDD_VDD") (pintype "power_in"))
      (node (ref "LED21") (pin "VDD") (pinfunction "VDD_VDD") (pintype "power_in"))
      (node (ref "LED22") (pin "VDD") (pinfunction "VDD_VDD") (pintype "power_in"))
      (node (ref "LED23") (pin "VDD") (pinfunction "VDD_VDD") (pintype "power_in"))
      (node (ref "LED24") (pin "VDD") (pinfunction "VDD_VDD") (pintype "power_in"))
      (node (ref "LED25") (pin "VDD") (pinfunction "VDD_VDD") (pintype "power_in"))
      (node (ref "LED26") (pin "VDD") (pinfunction "VDD_VDD") (pintype "power_in"))
      (node (ref "LED27") (pin "VDD") (pinfunction "VDD_VDD") (pintype "power_in"))
      (node (ref "LED28") (pin "VDD") (pinfunction "VDD_VDD") (pintype "power_in"))
      (node (ref "LED29") (pin "VDD") (pinfunction "VDD_VDD") (pintype "power_in"))
      (node (ref "LED3") (pin "VDD") (pinfunction "VDD_VDD") (pintype "power_in"))
      (node (ref "LED30") (pin "VDD") (pinfunction "VDD_VDD") (pintype "power_in"))
      (node (ref "LED31") (pin "VDD") (pinfunction "VDD_VDD") (pintype "power_in"))
      (node (ref "LED32") (pin "VDD") (pinfunction "VDD_VDD") (pintype "power_in"))
      (node (ref "LED33") (pin "VDD") (pinfunction "VDD_VDD") (pintype "power_in"))
      (node (ref "LED34") (pin "VDD") (pinfunction "VDD_VDD") (pintype "power_in"))
      (node (ref "LED35") (pin "VDD") (pinfunction "VDD_VDD") (pintype "power_in"))
      (node (ref "LED36") (pin "VDD") (pinfunction "VDD_VDD") (pintype "power_in"))
      (node (ref "LED37") (pin "VDD") (pinfunction "VDD_VDD") (pintype "power_in"))
      (node (ref "LED38") (pin "VDD") (pinfunction "VDD_VDD") (pintype "power_in"))
      (node (ref "LED39") (pin "VDD") (pinfunction "VDD_VDD") (pintype "power_in"))
      (node (ref "LED4") (pin "VDD") (pinfunction "VDD_VDD") (pintype "power_in"))
      (node (ref "LED40") (pin "VDD") (pinfunction "VDD_VDD") (pintype "power_in"))
      (node (ref "LED41") (pin "VDD") (pinfunction "VDD_VDD") (pintype "power_in"))
      (node (ref "LED42") (pin "VDD") (pinfunction "VDD_VDD") (pintype "power_in"))
      (node (ref "LED43") (pin "VDD") (pinfunction "VDD_VDD") (pintype "power_in"))
      (node (ref "LED44") (pin "VDD") (pinfunction "VDD_VDD") (pintype "power_in"))
      (node (ref "LED45") (pin "VDD") (pinfunction "VDD_VDD") (pintype "power_in"))
      (node (ref "LED46") (pin "VDD") (pinfunction "VDD_VDD") (pintype "power_in"))
      (node (ref "LED47") (pin "VDD") (pinfunction "VDD_VDD") (pintype "power_in"))
      (node (ref "LED48") (pin "VDD") (pinfunction "VDD_VDD") (pintype "power_in"))
      (node (ref "LED49") (pin "VDD") (pinfunction "VDD_VDD") (pintype "power_in"))
      (node (ref "LED5") (pin "VDD") (pinfunction "VDD_VDD") (pintype "power_in"))
      (node (ref "LED50") (pin "VDD") (pinfunction "VDD_VDD") (pintype "power_in"))
      (node (ref "LED51") (pin "VDD") (pinfunction "VDD_VDD") (pintype "power_in"))
      (node (ref "LED52") (pin "VDD") (pinfunction "VDD_VDD") (pintype "power_in"))
      (node (ref "LED53") (pin "VDD") (pinfunction "VDD_VDD") (pintype "power_in"))
      (node (ref "LED54") (pin "VDD") (pinfunction "VDD_VDD") (pintype "power_in"))
      (node (ref "LED55") (pin "VDD") (pinfunction "VDD_VDD") (pintype "power_in"))
      (node (ref "LED56") (pin "VDD") (pinfunction "VDD_VDD") (pintype "power_in"))
      (node (ref "LED57") (pin "VDD") (pinfunction "VDD_VDD") (pintype "power_in"))
      (node (ref "LED58") (pin "VDD") (pinfunction "VDD_VDD") (pintype "power_in"))
      (node (ref "LED59") (pin "VDD") (pinfunction "VDD_VDD") (pintype "power_in"))
      (node (ref "LED6") (pin "VDD") (pinfunction "VDD_VDD") (pintype "power_in"))
      (node (ref "LED60") (pin "VDD") (pinfunction "VDD_VDD") (pintype "power_in"))
      (node (ref "LED7") (pin "VDD") (pinfunction "VDD_VDD") (pintype "power_in"))
      (node (ref "LED8") (pin "VDD") (pinfunction "VDD_VDD") (pintype "power_in"))
      (node (ref "LED9") (pin "VDD") (pinfunction "VDD_VDD") (pintype "power_in"))
      (node (ref "LTC4412") (pin "6") (pinfunction "SENSE_6") (pintype "bidirectional"))
      (node (ref "PUSHPULL") (pin "1") (pinfunction "1OE_1") (pintype "bidirectional"))
      (node (ref "PUSHPULL") (pin "14") (pinfunction "VCC_14") (pintype "bidirectional"))
      (node (ref "PUSHPULL") (pin "4") (pinfunction "2OE_4") (pintype "bidirectional"))
      (node (ref "R2") (pin "2") (pinfunction "2_2") (pintype "passive"))
      (node (ref "T1") (pin "1") (pinfunction "S_1") (pintype "passive"))
      (node (ref "T1") (pin "2") (pinfunction "S_2") (pintype "passive"))
      (node (ref "T1") (pin "3") (pinfunction "S_3") (pintype "passive"))
      (node (ref "T2") (pin "1") (pinfunction "S_1") (pintype "passive"))
      (node (ref "T2") (pin "2") (pinfunction "S_2") (pintype "passive"))
      (node (ref "T2") (pin "3") (pinfunction "S_3") (pintype "passive"))
    )
    (net (code "3") (name "D+") (class "Default")
      (node (ref "C69") (pin "2") (pinfunction "2_2") (pintype "passive"))
      (node (ref "MCU") (pin "71") (pinfunction "PA12_71") (pintype "bidirectional"))
      (node (ref "R5") (pin "2") (pinfunction "2_2") (pintype "passive"))
      (node (ref "R6") (pin "1") (pinfunction "1_1") (pintype "passive"))
    )
    (net (code "4") (name "D-") (class "Default")
      (node (ref "C70") (pin "2") (pinfunction "2_2") (pintype "passive"))
      (node (ref "MCU") (pin "70") (pinfunction "PA11_70") (pintype "bidirectional"))
      (node (ref "R4") (pin "2") (pinfunction "2_2") (pintype "passive"))
    )
    (net (code "5") (name "DATA_IN_1_HIGH") (class "Default")
      (node (ref "PUSHPULL") (pin "11") (pinfunction "4Y_11") (pintype "bidirectional"))
      (node (ref "R1") (pin "1") (pinfunction "1_1") (pintype "passive"))
    )
    (net (code "6") (name "DATA_IN_1_LOW") (class "Default")
      (node (ref "MCU") (pin "39") (pinfunction "PE9_39") (pintype "bidirectional"))
      (node (ref "PUSHPULL") (pin "12") (pinfunction "4A_12") (pintype "bidirectional"))
    )
    (net (code "7") (name "DATA_IN_2_HIGH") (class "Default")
      (node (ref "PUSHPULL") (pin "8") (pinfunction "3Y_8") (pintype "bidirectional"))
      (node (ref "R3") (pin "1") (pinfunction "1_1") (pintype "passive"))
    )
    (net (code "8") (name "DATA_IN_2_LOW") (class "Default")
      (node (ref "MCU") (pin "41") (pinfunction "PE11_41") (pintype "bidirectional"))
      (node (ref "PUSHPULL") (pin "9") (pinfunction "3A_9") (pintype "bidirectional"))
    )
    (net (code "9") (name "GND") (class "Default")
      (node (ref "C1") (pin "2") (pinfunction "2_2") (pintype "passive"))
      (node (ref "C10") (pin "2") (pinfunction "2_2") (pintype "passive"))
      (node (ref "C11") (pin "2") (pinfunction "2_2") (pintype "passive"))
      (node (ref "C12") (pin "2") (pinfunction "2_2") (pintype "passive"))
      (node (ref "C13") (pin "2") (pinfunction "2_2") (pintype "passive"))
      (node (ref "C14") (pin "2") (pinfunction "2_2") (pintype "passive"))
      (node (ref "C15") (pin "2") (pinfunction "2_2") (pintype "passive"))
      (node (ref "C16") (pin "2") (pinfunction "2_2") (pintype "passive"))
      (node (ref "C17") (pin "2") (pinfunction "2_2") (pintype "passive"))
      (node (ref "C18") (pin "2") (pinfunction "2_2") (pintype "passive"))
      (node (ref "C19") (pin "2") (pinfunction "2_2") (pintype "passive"))
      (node (ref "C2") (pin "2") (pinfunction "2_2") (pintype "passive"))
      (node (ref "C20") (pin "2") (pinfunction "2_2") (pintype "passive"))
      (node (ref "C21") (pin "2") (pinfunction "2_2") (pintype "passive"))
      (node (ref "C22") (pin "2") (pinfunction "2_2") (pintype "passive"))
      (node (ref "C23") (pin "2") (pinfunction "2_2") (pintype "passive"))
      (node (ref "C24") (pin "2") (pinfunction "2_2") (pintype "passive"))
      (node (ref "C25") (pin "2") (pinfunction "2_2") (pintype "passive"))
      (node (ref "C26") (pin "2") (pinfunction "2_2") (pintype "passive"))
      (node (ref "C27") (pin "2") (pinfunction "2_2") (pintype "passive"))
      (node (ref "C28") (pin "2") (pinfunction "2_2") (pintype "passive"))
      (node (ref "C29") (pin "2") (pinfunction "2_2") (pintype "passive"))
      (node (ref "C3") (pin "2") (pinfunction "2_2") (pintype "passive"))
      (node (ref "C30") (pin "2") (pinfunction "2_2") (pintype "passive"))
      (node (ref "C31") (pin "2") (pinfunction "2_2") (pintype "passive"))
      (node (ref "C32") (pin "2") (pinfunction "2_2") (pintype "passive"))
      (node (ref "C33") (pin "2") (pinfunction "2_2") (pintype "passive"))
      (node (ref "C34") (pin "2") (pinfunction "2_2") (pintype "passive"))
      (node (ref "C35") (pin "2") (pinfunction "2_2") (pintype "passive"))
      (node (ref "C36") (pin "2") (pinfunction "2_2") (pintype "passive"))
      (node (ref "C37") (pin "2") (pinfunction "2_2") (pintype "passive"))
      (node (ref "C38") (pin "2") (pinfunction "2_2") (pintype "passive"))
      (node (ref "C39") (pin "2") (pinfunction "2_2") (pintype "passive"))
      (node (ref "C4") (pin "2") (pinfunction "2_2") (pintype "passive"))
      (node (ref "C40") (pin "2") (pinfunction "2_2") (pintype "passive"))
      (node (ref "C41") (pin "2") (pinfunction "2_2") (pintype "passive"))
      (node (ref "C42") (pin "2") (pinfunction "2_2") (pintype "passive"))
      (node (ref "C43") (pin "2") (pinfunction "2_2") (pintype "passive"))
      (node (ref "C44") (pin "2") (pinfunction "2_2") (pintype "passive"))
      (node (ref "C45") (pin "2") (pinfunction "2_2") (pintype "passive"))
      (node (ref "C46") (pin "2") (pinfunction "2_2") (pintype "passive"))
      (node (ref "C47") (pin "2") (pinfunction "2_2") (pintype "passive"))
      (node (ref "C48") (pin "2") (pinfunction "2_2") (pintype "passive"))
      (node (ref "C49") (pin "2") (pinfunction "2_2") (pintype "passive"))
      (node (ref "C5") (pin "2") (pinfunction "2_2") (pintype "passive"))
      (node (ref "C50") (pin "2") (pinfunction "2_2") (pintype "passive"))
      (node (ref "C51") (pin "2") (pinfunction "2_2") (pintype "passive"))
      (node (ref "C52") (pin "2") (pinfunction "2_2") (pintype "passive"))
      (node (ref "C53") (pin "2") (pinfunction "2_2") (pintype "passive"))
      (node (ref "C54") (pin "2") (pinfunction "2_2") (pintype "passive"))
      (node (ref "C55") (pin "2") (pinfunction "2_2") (pintype "passive"))
      (node (ref "C56") (pin "2") (pinfunction "2_2") (pintype "passive"))
      (node (ref "C57") (pin "2") (pinfunction "2_2") (pintype "passive"))
      (node (ref "C58") (pin "2") (pinfunction "2_2") (pintype "passive"))
      (node (ref "C59") (pin "2") (pinfunction "2_2") (pintype "passive"))
      (node (ref "C6") (pin "2") (pinfunction "2_2") (pintype "passive"))
      (node (ref "C60") (pin "2") (pinfunction "2_2") (pintype "passive"))
      (node (ref "C61") (pin "1") (pinfunction "1_1") (pintype "passive"))
      (node (ref "C62") (pin "2") (pinfunction "2_2") (pintype "passive"))
      (node (ref "C63") (pin "2") (pinfunction "2_2") (pintype "passive"))
      (node (ref "C64") (pin "2") (pinfunction "2_2") (pintype "passive"))
      (node (ref "C65") (pin "2") (pinfunction "2_2") (pintype "passive"))
      (node (ref "C66") (pin "2") (pinfunction "2_2") (pintype "passive"))
      (node (ref "C67") (pin "1") (pinfunction "1_1") (pintype "passive"))
      (node (ref "C68") (pin "1") (pinfunction "1_1") (pintype "passive"))
      (node (ref "C69") (pin "1") (pinfunction "1_1") (pintype "passive"))
      (node (ref "C7") (pin "2") (pinfunction "2_2") (pintype "passive"))
      (node (ref "C70") (pin "1") (pinfunction "1_1") (pintype "passive"))
      (node (ref "C71") (pin "2") (pinfunction "2_2") (pintype "passive"))
      (node (ref "C72") (pin "2") (pinfunction "2_2") (pintype "passive"))
      (node (ref "C73") (pin "2") (pinfunction "2_2") (pintype "passive"))
      (node (ref "C74") (pin "2") (pinfunction "2_2") (pintype "passive"))
      (node (ref "C75") (pin "2") (pinfunction "2_2") (pintype "passive"))
      (node (ref "C76") (pin "2") (pinfunction "2_2") (pintype "passive"))
      (node (ref "C77") (pin "2") (pinfunction "2_2") (pintype "passive"))
      (node (ref "C78") (pin "2") (pinfunction "2_2") (pintype "passive"))
      (node (ref "C79") (pin "2") (pinfunction "2_2") (pintype "passive"))
      (node (ref "C8") (pin "2") (pinfunction "2_2") (pintype "passive"))
      (node (ref "C80") (pin "2") (pinfunction "2_2") (pintype "passive"))
      (node (ref "C9") (pin "2") (pinfunction "2_2") (pintype "passive"))
      (node (ref "D1") (pin "2") (pinfunction "GND_2") (pintype "power_in"))
      (node (ref "JP1") (pin "10") (pinfunction "10_10") (pintype "passive"))
      (node (ref "JP1") (pin "12") (pinfunction "12_12") (pintype "passive"))
      (node (ref "JP1") (pin "14") (pinfunction "14_14") (pintype "passive"))
      (node (ref "JP1") (pin "16") (pinfunction "16_16") (pintype "passive"))
      (node (ref "JP1") (pin "18") (pinfunction "18_18") (pintype "passive"))
      (node (ref "JP1") (pin "20") (pinfunction "20_20") (pintype "passive"))
      (node (ref "JP1") (pin "4") (pinfunction "4_4") (pintype "passive"))
      (node (ref "JP1") (pin "6") (pinfunction "6_6") (pintype "passive"))
      (node (ref "JP1") (pin "8") (pinfunction "8_8") (pintype "passive"))
      (node (ref "K1") (pin "2") (pinfunction "2_2") (pintype "passive"))
      (node (ref "K1") (pin "3") (pinfunction "3_3") (pintype "passive"))
      (node (ref "LDO") (pin "2") (pinfunction "GND_2") (pintype "bidirectional"))
      (node (ref "LED1") (pin "VSS") (pinfunction "GND_VSS") (pintype "power_in"))
      (node (ref "LED10") (pin "VSS") (pinfunction "GND_VSS") (pintype "power_in"))
      (node (ref "LED11") (pin "VSS") (pinfunction "GND_VSS") (pintype "power_in"))
      (node (ref "LED12") (pin "VSS") (pinfunction "GND_VSS") (pintype "power_in"))
      (node (ref "LED13") (pin "VSS") (pinfunction "GND_VSS") (pintype "power_in"))
      (node (ref "LED14") (pin "VSS") (pinfunction "GND_VSS") (pintype "power_in"))
      (node (ref "LED15") (pin "VSS") (pinfunction "GND_VSS") (pintype "power_in"))
      (node (ref "LED16") (pin "VSS") (pinfunction "GND_VSS") (pintype "power_in"))
      (node (ref "LED17") (pin "VSS") (pinfunction "GND_VSS") (pintype "power_in"))
      (node (ref "LED18") (pin "VSS") (pinfunction "GND_VSS") (pintype "power_in"))
      (node (ref "LED19") (pin "VSS") (pinfunction "GND_VSS") (pintype "power_in"))
      (node (ref "LED2") (pin "VSS") (pinfunction "GND_VSS") (pintype "power_in"))
      (node (ref "LED20") (pin "VSS") (pinfunction "GND_VSS") (pintype "power_in"))
      (node (ref "LED21") (pin "VSS") (pinfunction "GND_VSS") (pintype "power_in"))
      (node (ref "LED22") (pin "VSS") (pinfunction "GND_VSS") (pintype "power_in"))
      (node (ref "LED23") (pin "VSS") (pinfunction "GND_VSS") (pintype "power_in"))
      (node (ref "LED24") (pin "VSS") (pinfunction "GND_VSS") (pintype "power_in"))
      (node (ref "LED25") (pin "VSS") (pinfunction "GND_VSS") (pintype "power_in"))
      (node (ref "LED26") (pin "VSS") (pinfunction "GND_VSS") (pintype "power_in"))
      (node (ref "LED27") (pin "VSS") (pinfunction "GND_VSS") (pintype "power_in"))
      (node (ref "LED28") (pin "VSS") (pinfunction "GND_VSS") (pintype "power_in"))
      (node (ref "LED29") (pin "VSS") (pinfunction "GND_VSS") (pintype "power_in"))
      (node (ref "LED3") (pin "VSS") (pinfunction "GND_VSS") (pintype "power_in"))
      (node (ref "LED30") (pin "VSS") (pinfunction "GND_VSS") (pintype "power_in"))
      (node (ref "LED31") (pin "VSS") (pinfunction "GND_VSS") (pintype "power_in"))
      (node (ref "LED32") (pin "VSS") (pinfunction "GND_VSS") (pintype "power_in"))
      (node (ref "LED33") (pin "VSS") (pinfunction "GND_VSS") (pintype "power_in"))
      (node (ref "LED34") (pin "VSS") (pinfunction "GND_VSS") (pintype "power_in"))
      (node (ref "LED35") (pin "VSS") (pinfunction "GND_VSS") (pintype "power_in"))
      (node (ref "LED36") (pin "VSS") (pinfunction "GND_VSS") (pintype "power_in"))
      (node (ref "LED37") (pin "VSS") (pinfunction "GND_VSS") (pintype "power_in"))
      (node (ref "LED38") (pin "VSS") (pinfunction "GND_VSS") (pintype "power_in"))
      (node (ref "LED39") (pin "VSS") (pinfunction "GND_VSS") (pintype "power_in"))
      (node (ref "LED4") (pin "VSS") (pinfunction "GND_VSS") (pintype "power_in"))
      (node (ref "LED40") (pin "VSS") (pinfunction "GND_VSS") (pintype "power_in"))
      (node (ref "LED41") (pin "VSS") (pinfunction "GND_VSS") (pintype "power_in"))
      (node (ref "LED42") (pin "VSS") (pinfunction "GND_VSS") (pintype "power_in"))
      (node (ref "LED43") (pin "VSS") (pinfunction "GND_VSS") (pintype "power_in"))
      (node (ref "LED44") (pin "VSS") (pinfunction "GND_VSS") (pintype "power_in"))
      (node (ref "LED45") (pin "VSS") (pinfunction "GND_VSS") (pintype "power_in"))
      (node (ref "LED46") (pin "VSS") (pinfunction "GND_VSS") (pintype "power_in"))
      (node (ref "LED47") (pin "VSS") (pinfunction "GND_VSS") (pintype "power_in"))
      (node (ref "LED48") (pin "VSS") (pinfunction "GND_VSS") (pintype "power_in"))
      (node (ref "LED49") (pin "VSS") (pinfunction "GND_VSS") (pintype "power_in"))
      (node (ref "LED5") (pin "VSS") (pinfunction "GND_VSS") (pintype "power_in"))
      (node (ref "LED50") (pin "VSS") (pinfunction "GND_VSS") (pintype "power_in"))
      (node (ref "LED51") (pin "VSS") (pinfunction "GND_VSS") (pintype "power_in"))
      (node (ref "LED52") (pin "VSS") (pinfunction "GND_VSS") (pintype "power_in"))
      (node (ref "LED53") (pin "VSS") (pinfunction "GND_VSS") (pintype "power_in"))
      (node (ref "LED54") (pin "VSS") (pinfunction "GND_VSS") (pintype "power_in"))
      (node (ref "LED55") (pin "VSS") (pinfunction "GND_VSS") (pintype "power_in"))
      (node (ref "LED56") (pin "VSS") (pinfunction "GND_VSS") (pintype "power_in"))
      (node (ref "LED57") (pin "VSS") (pinfunction "GND_VSS") (pintype "power_in"))
      (node (ref "LED58") (pin "VSS") (pinfunction "GND_VSS") (pintype "power_in"))
      (node (ref "LED59") (pin "VSS") (pinfunction "GND_VSS") (pintype "power_in"))
      (node (ref "LED6") (pin "VSS") (pinfunction "GND_VSS") (pintype "power_in"))
      (node (ref "LED60") (pin "VSS") (pinfunction "GND_VSS") (pintype "power_in"))
      (node (ref "LED7") (pin "VSS") (pinfunction "GND_VSS") (pintype "power_in"))
      (node (ref "LED8") (pin "VSS") (pinfunction "GND_VSS") (pintype "power_in"))
      (node (ref "LED9") (pin "VSS") (pinfunction "GND_VSS") (pintype "power_in"))
      (node (ref "LTC4412") (pin "2") (pinfunction "GND_2") (pintype "bidirectional"))
      (node (ref "LTC4412") (pin "3") (pinfunction "CTL_3") (pintype "bidirectional"))
      (node (ref "MCU") (pin "10") (pinfunction "VSS1_10") (pintype "power_in"))
      (node (ref "MCU") (pin "19") (pinfunction "VSSA_19") (pintype "power_in"))
      (node (ref "MCU") (pin "26") (pinfunction "VSS2_26") (pintype "power_in"))
      (node (ref "MCU") (pin "49") (pinfunction "VSS3_49") (pintype "power_in"))
      (node (ref "MCU") (pin "74") (pinfunction "VSS4_74") (pintype "power_in"))
      (node (ref "MCU") (pin "99") (pinfunction "VSS5_99") (pintype "power_in"))
      (node (ref "PUSHPULL") (pin "10") (pinfunction "3OE_10") (pintype "bidirectional"))
      (node (ref "PUSHPULL") (pin "13") (pinfunction "4OE_13") (pintype "bidirectional"))
      (node (ref "PUSHPULL") (pin "3") (pinfunction "1Y_3") (pintype "bidirectional"))
      (node (ref "PUSHPULL") (pin "6") (pinfunction "2Y_6") (pintype "bidirectional"))
      (node (ref "PUSHPULL") (pin "7") (pinfunction "GND_7") (pintype "bidirectional"))
      (node (ref "R6") (pin "2") (pinfunction "2_2") (pintype "passive"))
      (node (ref "R7") (pin "2") (pinfunction "2_2") (pintype "passive"))
      (node (ref "R8") (pin "2") (pinfunction "2_2") (pintype "passive"))
      (node (ref "R9") (pin "2") (pinfunction "2_2") (pintype "passive"))
      (node (ref "X1") (pin "GND") (pinfunction "GND_GND") (pintype "bidirectional"))
    )
    (net (code "10") (name "JTCK") (class "Default")
      (node (ref "JP1") (pin "9") (pinfunction "9_9") (pintype "passive"))
      (node (ref "MCU") (pin "76") (pinfunction "PA14_76") (pintype "bidirectional"))
    )
    (net (code "11") (name "JTDI") (class "Default")
      (node (ref "JP1") (pin "5") (pinfunction "5_5") (pintype "passive"))
      (node (ref "MCU") (pin "77") (pinfunction "PA15_77") (pintype "bidirectional"))
    )
    (net (code "12") (name "JTDO") (class "Default")
      (node (ref "JP1") (pin "13") (pinfunction "13_13") (pintype "passive"))
      (node (ref "MCU") (pin "89") (pinfunction "PB3_89") (pintype "bidirectional"))
    )
    (net (code "13") (name "JTMS") (class "Default")
      (node (ref "JP1") (pin "7") (pinfunction "7_7") (pintype "passive"))
      (node (ref "MCU") (pin "72") (pinfunction "PA13_72") (pintype "bidirectional"))
    )
    (net (code "14") (name "NJTRST") (class "Default")
      (node (ref "JP1") (pin "3") (pinfunction "3_3") (pintype "passive"))
      (node (ref "MCU") (pin "90") (pinfunction "PB4_90") (pintype "bidirectional"))
    )
    (net (code "15") (name "NRSTIN") (class "Default")
      (node (ref "JP1") (pin "15") (pinfunction "15_15") (pintype "passive"))
      (node (ref "MCU") (pin "14") (pinfunction "NRST_14") (pintype "bidirectional"))
    )
    (net (code "16") (name "Net-(0.5-I)") (class "Default")
      (node (ref "0.5") (pin "P$1") (pinfunction "I_P$1") (pintype "bidirectional"))
      (node (ref "D3") (pin "1") (pinfunction "C_1") (pintype "passive"))
    )
    (net (code "17") (name "Net-(4-I)") (class "Default")
      (node (ref "4") (pin "P$1") (pinfunction "I_P$1") (pintype "bidirectional"))
      (node (ref "K1") (pin "1") (pinfunction "1_1") (pintype "passive"))
    )
    (net (code "18") (name "Net-(4-O)") (class "Default")
      (node (ref "4") (pin "P$2") (pinfunction "O_P$2") (pintype "bidirectional"))
      (node (ref "C80") (pin "1") (pinfunction "1_1") (pintype "passive"))
      (node (ref "LTC4412") (pin "1") (pinfunction "VIN_1") (pintype "bidirectional"))
      (node (ref "T2") (pin "5") (pinfunction "D_5") (pintype "passive"))
      (node (ref "T2") (pin "6") (pinfunction "D_6") (pintype "passive"))
      (node (ref "T2") (pin "7") (pinfunction "D_7") (pintype "passive"))
      (node (ref "T2") (pin "8") (pinfunction "D_8") (pintype "passive"))
    )
    (net (code "19") (name "Net-(D1-2)") (class "Default")
      (node (ref "D1") (pin "3") (pinfunction "2_3") (pintype "passive"))
      (node (ref "L1") (pin "3") (pinfunction "2_3") (pintype "passive"))
    )
    (net (code "20") (name "Net-(D1-3)") (class "Default")
      (node (ref "D1") (pin "4") (pinfunction "3_4") (pintype "passive"))
      (node (ref "R5") (pin "1") (pinfunction "1_1") (pintype "passive"))
    )
    (net (code "21") (name "Net-(D1-4)") (class "Default")
      (node (ref "D1") (pin "6") (pinfunction "4_6") (pintype "passive"))
      (node (ref "R4") (pin "1") (pinfunction "1_1") (pintype "passive"))
    )
    (net (code "22") (name "Net-(JP1-Pad11)") (class "Default")
      (node (ref "JP1") (pin "11") (pinfunction "11_11") (pintype "passive"))
      (node (ref "R9") (pin "1") (pinfunction "1_1") (pintype "passive"))
    )
    (net (code "23") (name "Net-(JP1-Pad17)") (class "Default")
      (node (ref "JP1") (pin "17") (pinfunction "17_17") (pintype "passive"))
      (node (ref "R8") (pin "1") (pinfunction "1_1") (pintype "passive"))
    )
    (net (code "24") (name "Net-(JP1-Pad19)") (class "Default")
      (node (ref "JP1") (pin "19") (pinfunction "19_19") (pintype "passive"))
      (node (ref "R7") (pin "1") (pinfunction "1_1") (pintype "passive"))
    )
    (net (code "25") (name "Net-(L1-1)") (class "Default")
      (node (ref "L1") (pin "4") (pinfunction "1_4") (pintype "passive"))
      (node (ref "X1") (pin "D+") (pinfunction "D+_D+") (pintype "bidirectional"))
    )
    (net (code "26") (name "Net-(L1-3)") (class "Default")
      (node (ref "D1") (pin "1") (pinfunction "1_1") (pintype "passive"))
      (node (ref "L1") (pin "2") (pinfunction "3_2") (pintype "passive"))
    )
    (net (code "27") (name "Net-(L1-4)") (class "Default")
      (node (ref "L1") (pin "1") (pinfunction "4_1") (pintype "passive"))
      (node (ref "X1") (pin "D-") (pinfunction "D-_D-") (pintype "bidirectional"))
    )
    (net (code "28") (name "Net-(LED1-DI)") (class "Default")
      (node (ref "LED1") (pin "DIN") (pinfunction "DI_DIN") (pintype "input"))
      (node (ref "LED30") (pin "DOUT") (pinfunction "DO_DOUT") (pintype "output"))
    )
    (net (code "29") (name "Net-(LED1-DO)") (class "Default")
      (node (ref "LED1") (pin "DOUT") (pinfunction "DO_DOUT") (pintype "output"))
      (node (ref "LED2") (pin "DIN") (pinfunction "DI_DIN") (pintype "input"))
    )
    (net (code "30") (name "Net-(LED2-DO)") (class "Default")
      (node (ref "LED2") (pin "DOUT") (pinfunction "DO_DOUT") (pintype "output"))
      (node (ref "LED3") (pin "DIN") (pinfunction "DI_DIN") (pintype "input"))
    )
    (net (code "31") (name "Net-(LED3-DO)") (class "Default")
      (node (ref "LED3") (pin "DOUT") (pinfunction "DO_DOUT") (pintype "output"))
      (node (ref "LED4") (pin "DIN") (pinfunction "DI_DIN") (pintype "input"))
    )
    (net (code "32") (name "Net-(LED4-DO)") (class "Default")
      (node (ref "LED4") (pin "DOUT") (pinfunction "DO_DOUT") (pintype "output"))
      (node (ref "LED5") (pin "DIN") (pinfunction "DI_DIN") (pintype "input"))
    )
    (net (code "33") (name "Net-(LED5-DO)") (class "Default")
      (node (ref "LED5") (pin "DOUT") (pinfunction "DO_DOUT") (pintype "output"))
      (node (ref "LED6") (pin "DIN") (pinfunction "DI_DIN") (pintype "input"))
    )
    (net (code "34") (name "Net-(LED7-DI)") (class "Default")
      (node (ref "LED7") (pin "DIN") (pinfunction "DI_DIN") (pintype "input"))
      (node (ref "R3") (pin "2") (pinfunction "2_2") (pintype "passive"))
    )
    (net (code "35") (name "Net-(LED7-DO)") (class "Default")
      (node (ref "LED7") (pin "DOUT") (pinfunction "DO_DOUT") (pintype "output"))
      (node (ref "LED8") (pin "DIN") (pinfunction "DI_DIN") (pintype "input"))
    )
    (net (code "36") (name "Net-(LED8-DO)") (class "Default")
      (node (ref "LED8") (pin "DOUT") (pinfunction "DO_DOUT") (pintype "output"))
      (node (ref "LED9") (pin "DIN") (pinfunction "DI_DIN") (pintype "input"))
    )
    (net (code "37") (name "Net-(LED10-DI)") (class "Default")
      (node (ref "LED10") (pin "DIN") (pinfunction "DI_DIN") (pintype "input"))
      (node (ref "LED9") (pin "DOUT") (pinfunction "DO_DOUT") (pintype "output"))
    )
    (net (code "38") (name "Net-(LED10-DO)") (class "Default")
      (node (ref "LED10") (pin "DOUT") (pinfunction "DO_DOUT") (pintype "output"))
      (node (ref "LED11") (pin "DIN") (pinfunction "DI_DIN") (pintype "input"))
    )
    (net (code "39") (name "Net-(LED11-DO)") (class "Default")
      (node (ref "LED11") (pin "DOUT") (pinfunction "DO_DOUT") (pintype "output"))
      (node (ref "LED12") (pin "DIN") (pinfunction "DI_DIN") (pintype "input"))
    )
    (net (code "40") (name "Net-(LED12-DO)") (class "Default")
      (node (ref "LED12") (pin "DOUT") (pinfunction "DO_DOUT") (pintype "output"))
      (node (ref "LED13") (pin "DIN") (pinfunction "DI_DIN") (pintype "input"))
    )
    (net (code "41") (name "Net-(LED13-DO)") (class "Default")
      (node (ref "LED13") (pin "DOUT") (pinfunction "DO_DOUT") (pintype "output"))
      (node (ref "LED14") (pin "DIN") (pinfunction "DI_DIN") (pintype "input"))
    )
    (net (code "42") (name "Net-(LED14-DO)") (class "Default")
      (node (ref "LED14") (pin "DOUT") (pinfunction "DO_DOUT") (pintype "output"))
      (node (ref "LED15") (pin "DIN") (pinfunction "DI_DIN") (pintype "input"))
    )
    (net (code "43") (name "Net-(LED15-DO)") (class "Default")
      (node (ref "LED15") (pin "DOUT") (pinfunction "DO_DOUT") (pintype "output"))
      (node (ref "LED16") (pin "DIN") (pinfunction "DI_DIN") (pintype "input"))
    )
    (net (code "44") (name "Net-(LED16-DO)") (class "Default")
      (node (ref "LED16") (pin "DOUT") (pinfunction "DO_DOUT") (pintype "output"))
      (node (ref "LED17") (pin "DIN") (pinfunction "DI_DIN") (pintype "input"))
    )
    (net (code "45") (name "Net-(LED17-DO)") (class "Default")
      (node (ref "LED17") (pin "DOUT") (pinfunction "DO_DOUT") (pintype "output"))
      (node (ref "LED18") (pin "DIN") (pinfunction "DI_DIN") (pintype "input"))
    )
    (net (code "46") (name "Net-(LED18-DO)") (class "Default")
      (node (ref "LED18") (pin "DOUT") (pinfunction "DO_DOUT") (pintype "output"))
      (node (ref "LED19") (pin "DIN") (pinfunction "DI_DIN") (pintype "input"))
    )
    (net (code "47") (name "Net-(LED19-DO)") (class "Default")
      (node (ref "LED19") (pin "DOUT") (pinfunction "DO_DOUT") (pintype "output"))
      (node (ref "LED20") (pin "DIN") (pinfunction "DI_DIN") (pintype "input"))
    )
    (net (code "48") (name "Net-(LED20-DO)") (class "Default")
      (node (ref "LED20") (pin "DOUT") (pinfunction "DO_DOUT") (pintype "output"))
      (node (ref "LED21") (pin "DIN") (pinfunction "DI_DIN") (pintype "input"))
    )
    (net (code "49") (name "Net-(LED21-DO)") (class "Default")
      (node (ref "LED21") (pin "DOUT") (pinfunction "DO_DOUT") (pintype "output"))
      (node (ref "LED22") (pin "DIN") (pinfunction "DI_DIN") (pintype "input"))
    )
    (net (code "50") (name "Net-(LED22-DO)") (class "Default")
      (node (ref "LED22") (pin "DOUT") (pinfunction "DO_DOUT") (pintype "output"))
      (node (ref "LED23") (pin "DIN") (pinfunction "DI_DIN") (pintype "input"))
    )
    (net (code "51") (name "Net-(LED23-DO)") (class "Default")
      (node (ref "LED23") (pin "DOUT") (pinfunction "DO_DOUT") (pintype "output"))
      (node (ref "LED24") (pin "DIN") (pinfunction "DI_DIN") (pintype "input"))
    )
    (net (code "52") (name "Net-(LED24-DO)") (class "Default")
      (node (ref "LED24") (pin "DOUT") (pinfunction "DO_DOUT") (pintype "output"))
      (node (ref "LED25") (pin "DIN") (pinfunction "DI_DIN") (pintype "input"))
    )
    (net (code "53") (name "Net-(LED25-DO)") (class "Default")
      (node (ref "LED25") (pin "DOUT") (pinfunction "DO_DOUT") (pintype "output"))
      (node (ref "LED26") (pin "DIN") (pinfunction "DI_DIN") (pintype "input"))
    )
    (net (code "54") (name "Net-(LED26-DO)") (class "Default")
      (node (ref "LED26") (pin "DOUT") (pinfunction "DO_DOUT") (pintype "output"))
      (node (ref "LED27") (pin "DIN") (pinfunction "DI_DIN") (pintype "input"))
    )
    (net (code "55") (name "Net-(LED27-DO)") (class "Default")
      (node (ref "LED27") (pin "DOUT") (pinfunction "DO_DOUT") (pintype "output"))
      (node (ref "LED28") (pin "DIN") (pinfunction "DI_DIN") (pintype "input"))
    )
    (net (code "56") (name "Net-(LED28-DO)") (class "Default")
      (node (ref "LED28") (pin "DOUT") (pinfunction "DO_DOUT") (pintype "output"))
      (node (ref "LED29") (pin "DIN") (pinfunction "DI_DIN") (pintype "input"))
    )
    (net (code "57") (name "Net-(LED29-DO)") (class "Default")
      (node (ref "LED29") (pin "DOUT") (pinfunction "DO_DOUT") (pintype "output"))
      (node (ref "LED30") (pin "DIN") (pinfunction "DI_DIN") (pintype "input"))
    )
    (net (code "58") (name "Net-(LED31-DI)") (class "Default")
      (node (ref "LED31") (pin "DIN") (pinfunction "DI_DIN") (pintype "input"))
      (node (ref "LED60") (pin "DOUT") (pinfunction "DO_DOUT") (pintype "output"))
    )
    (net (code "59") (name "Net-(LED31-DO)") (class "Default")
      (node (ref "LED31") (pin "DOUT") (pinfunction "DO_DOUT") (pintype "output"))
      (node (ref "LED32") (pin "DIN") (pinfunction "DI_DIN") (pintype "input"))
    )
    (net (code "60") (name "Net-(LED32-DO)") (class "Default")
      (node (ref "LED32") (pin "DOUT") (pinfunction "DO_DOUT") (pintype "output"))
      (node (ref "LED33") (pin "DIN") (pinfunction "DI_DIN") (pintype "input"))
    )
    (net (code "61") (name "Net-(LED33-DO)") (class "Default")
      (node (ref "LED33") (pin "DOUT") (pinfunction "DO_DOUT") (pintype "output"))
      (node (ref "LED34") (pin "DIN") (pinfunction "DI_DIN") (pintype "input"))
    )
    (net (code "62") (name "Net-(LED34-DO)") (class "Default")
      (node (ref "LED34") (pin "DOUT") (pinfunction "DO_DOUT") (pintype "output"))
      (node (ref "LED35") (pin "DIN") (pinfunction "DI_DIN") (pintype "input"))
    )
    (net (code "63") (name "Net-(LED35-DO)") (class "Default")
      (node (ref "LED35") (pin "DOUT") (pinfunction "DO_DOUT") (pintype "output"))
      (node (ref "LED36") (pin "DIN") (pinfunction "DI_DIN") (pintype "input"))
    )
    (net (code "64") (name "Net-(LED36-DO)") (class "Default")
      (node (ref "LED36") (pin "DOUT") (pinfunction "DO_DOUT") (pintype "output"))
      (node (ref "LED37") (pin "DIN") (pinfunction "DI_DIN") (pintype "input"))
    )
    (net (code "65") (name "Net-(LED38-DI)") (class "Default")
      (node (ref "LED38") (pin "DIN") (pinfunction "DI_DIN") (pintype "input"))
      (node (ref "R1") (pin "2") (pinfunction "2_2") (pintype "passive"))
    )
    (net (code "66") (name "Net-(LED38-DO)") (class "Default")
      (node (ref "LED38") (pin "DOUT") (pinfunction "DO_DOUT") (pintype "output"))
      (node (ref "LED39") (pin "DIN") (pinfunction "DI_DIN") (pintype "input"))
    )
    (net (code "67") (name "Net-(LED39-DO)") (class "Default")
      (node (ref "LED39") (pin "DOUT") (pinfunction "DO_DOUT") (pintype "output"))
      (node (ref "LED40") (pin "DIN") (pinfunction "DI_DIN") (pintype "input"))
    )
    (net (code "68") (name "Net-(LED40-DO)") (class "Default")
      (node (ref "LED40") (pin "DOUT") (pinfunction "DO_DOUT") (pintype "output"))
      (node (ref "LED41") (pin "DIN") (pinfunction "DI_DIN") (pintype "input"))
    )
    (net (code "69") (name "Net-(LED41-DO)") (class "Default")
      (node (ref "LED41") (pin "DOUT") (pinfunction "DO_DOUT") (pintype "output"))
      (node (ref "LED42") (pin "DIN") (pinfunction "DI_DIN") (pintype "input"))
    )
    (net (code "70") (name "Net-(LED42-DO)") (class "Default")
      (node (ref "LED42") (pin "DOUT") (pinfunction "DO_DOUT") (pintype "output"))
      (node (ref "LED43") (pin "DIN") (pinfunction "DI_DIN") (pintype "input"))
    )
    (net (code "71") (name "Net-(LED43-DO)") (class "Default")
      (node (ref "LED43") (pin "DOUT") (pinfunction "DO_DOUT") (pintype "output"))
      (node (ref "LED44") (pin "DIN") (pinfunction "DI_DIN") (pintype "input"))
    )
    (net (code "72") (name "Net-(LED44-DO)") (class "Default")
      (node (ref "LED44") (pin "DOUT") (pinfunction "DO_DOUT") (pintype "output"))
      (node (ref "LED45") (pin "DIN") (pinfunction "DI_DIN") (pintype "input"))
    )
    (net (code "73") (name "Net-(LED45-DO)") (class "Default")
      (node (ref "LED45") (pin "DOUT") (pinfunction "DO_DOUT") (pintype "output"))
      (node (ref "LED46") (pin "DIN") (pinfunction "DI_DIN") (pintype "input"))
    )
    (net (code "74") (name "Net-(LED46-DO)") (class "Default")
      (node (ref "LED46") (pin "DOUT") (pinfunction "DO_DOUT") (pintype "output"))
      (node (ref "LED47") (pin "DIN") (pinfunction "DI_DIN") (pintype "input"))
    )
    (net (code "75") (name "Net-(LED47-DO)") (class "Default")
      (node (ref "LED47") (pin "DOUT") (pinfunction "DO_DOUT") (pintype "output"))
      (node (ref "LED48") (pin "DIN") (pinfunction "DI_DIN") (pintype "input"))
    )
    (net (code "76") (name "Net-(LED48-DO)") (class "Default")
      (node (ref "LED48") (pin "DOUT") (pinfunction "DO_DOUT") (pintype "output"))
      (node (ref "LED49") (pin "DIN") (pinfunction "DI_DIN") (pintype "input"))
    )
    (net (code "77") (name "Net-(LED49-DO)") (class "Default")
      (node (ref "LED49") (pin "DOUT") (pinfunction "DO_DOUT") (pintype "output"))
      (node (ref "LED50") (pin "DIN") (pinfunction "DI_DIN") (pintype "input"))
    )
    (net (code "78") (name "Net-(LED50-DO)") (class "Default")
      (node (ref "LED50") (pin "DOUT") (pinfunction "DO_DOUT") (pintype "output"))
      (node (ref "LED51") (pin "DIN") (pinfunction "DI_DIN") (pintype "input"))
    )
    (net (code "79") (name "Net-(LED51-DO)") (class "Default")
      (node (ref "LED51") (pin "DOUT") (pinfunction "DO_DOUT") (pintype "output"))
      (node (ref "LED52") (pin "DIN") (pinfunction "DI_DIN") (pintype "input"))
    )
    (net (code "80") (name "Net-(LED52-DO)") (class "Default")
      (node (ref "LED52") (pin "DOUT") (pinfunction "DO_DOUT") (pintype "output"))
      (node (ref "LED53") (pin "DIN") (pinfunction "DI_DIN") (pintype "input"))
    )
    (net (code "81") (name "Net-(LED53-DO)") (class "Default")
      (node (ref "LED53") (pin "DOUT") (pinfunction "DO_DOUT") (pintype "output"))
      (node (ref "LED54") (pin "DIN") (pinfunction "DI_DIN") (pintype "input"))
    )
    (net (code "82") (name "Net-(LED54-DO)") (class "Default")
      (node (ref "LED54") (pin "DOUT") (pinfunction "DO_DOUT") (pintype "output"))
      (node (ref "LED55") (pin "DIN") (pinfunction "DI_DIN") (pintype "input"))
    )
    (net (code "83") (name "Net-(LED55-DO)") (class "Default")
      (node (ref "LED55") (pin "DOUT") (pinfunction "DO_DOUT") (pintype "output"))
      (node (ref "LED56") (pin "DIN") (pinfunction "DI_DIN") (pintype "input"))
    )
    (net (code "84") (name "Net-(LED56-DO)") (class "Default")
      (node (ref "LED56") (pin "DOUT") (pinfunction "DO_DOUT") (pintype "output"))
      (node (ref "LED57") (pin "DIN") (pinfunction "DI_DIN") (pintype "input"))
    )
    (net (code "85") (name "Net-(LED57-DO)") (class "Default")
      (node (ref "LED57") (pin "DOUT") (pinfunction "DO_DOUT") (pintype "output"))
      (node (ref "LED58") (pin "DIN") (pinfunction "DI_DIN") (pintype "input"))
    )
    (net (code "86") (name "Net-(LED58-DO)") (class "Default")
      (node (ref "LED58") (pin "DOUT") (pinfunction "DO_DOUT") (pintype "output"))
      (node (ref "LED59") (pin "DIN") (pinfunction "DI_DIN") (pintype "input"))
    )
    (net (code "87") (name "Net-(LED59-DO)") (class "Default")
      (node (ref "LED59") (pin "DOUT") (pinfunction "DO_DOUT") (pintype "output"))
      (node (ref "LED60") (pin "DIN") (pinfunction "DI_DIN") (pintype "input"))
    )
    (net (code "88") (name "Net-(LTC4412-GATE)") (class "Default")
      (node (ref "LTC4412") (pin "5") (pinfunction "GATE_5") (pintype "bidirectional"))
      (node (ref "T2") (pin "4") (pinfunction "G_4") (pintype "passive"))
    )
    (net (code "89") (name "Net-(MCU-VCAP1)") (class "Default")
      (node (ref "C77") (pin "1") (pinfunction "1_1") (pintype "passive"))
      (node (ref "MCU") (pin "48") (pinfunction "VCAP1_48") (pintype "bidirectional"))
    )
    (net (code "90") (name "Net-(MCU-VCAP2)") (class "Default")
      (node (ref "C76") (pin "1") (pinfunction "1_1") (pintype "passive"))
      (node (ref "MCU") (pin "73") (pinfunction "VCAP2_73") (pintype "bidirectional"))
    )
    (net (code "91") (name "OSC_IN") (class "Default")
      (node (ref "C74") (pin "1") (pinfunction "1_1") (pintype "passive"))
      (node (ref "MCU") (pin "12") (pinfunction "PH0-OSC_IN_12") (pintype "bidirectional"))
      (node (ref "Q1_24MHZ") (pin "1") (pinfunction "1_1") (pintype "passive"))
    )
    (net (code "92") (name "OSC_OUT") (class "Default")
      (node (ref "C75") (pin "1") (pinfunction "1_1") (pintype "passive"))
      (node (ref "MCU") (pin "13") (pinfunction "PH1-OSC_OUT_13") (pintype "bidirectional"))
      (node (ref "Q1_24MHZ") (pin "2") (pinfunction "2_2") (pintype "passive"))
    )
    (net (code "93") (name "PM_STATUS") (class "Default")
      (node (ref "LTC4412") (pin "4") (pinfunction "STAT_4") (pintype "bidirectional"))
      (node (ref "MCU") (pin "23") (pinfunction "PA1_23") (pintype "bidirectional"))
      (node (ref "R2") (pin "1") (pinfunction "1_1") (pintype "passive"))
      (node (ref "T1") (pin "4") (pinfunction "G_4") (pintype "passive"))
    )
    (net (code "94") (name "VBUS") (class "Default")
      (node (ref "C67") (pin "2") (pinfunction "2_2") (pintype "passive"))
      (node (ref "D3") (pin "3") (pinfunction "A_3") (pintype "passive"))
      (node (ref "X1") (pin "VBUS") (pinfunction "VBUS_VBUS") (pintype "bidirectional"))
    )
    (net (code "95") (name "VBUS_S") (class "Default")
      (node (ref "0.5") (pin "P$2") (pinfunction "O_P$2") (pintype "bidirectional"))
      (node (ref "C68") (pin "2") (pinfunction "2_2") (pintype "passive"))
      (node (ref "D1") (pin "5") (pinfunction "VDD_5") (pintype "power_in"))
      (node (ref "T1") (pin "5") (pinfunction "D_5") (pintype "passive"))
      (node (ref "T1") (pin "6") (pinfunction "D_6") (pintype "passive"))
      (node (ref "T1") (pin "7") (pinfunction "D_7") (pintype "passive"))
      (node (ref "T1") (pin "8") (pinfunction "D_8") (pintype "passive"))
    )
    (net (code "96") (name "unconnected-(LDO-NR-Pad4)") (class "Default")
      (node (ref "LDO") (pin "4") (pinfunction "NR_4") (pintype "bidirectional"))
    )
    (net (code "97") (name "unconnected-(LED6-DO-PadDOUT)") (class "Default")
      (node (ref "LED6") (pin "DOUT") (pinfunction "DO_DOUT") (pintype "output"))
    )
    (net (code "98") (name "unconnected-(LED37-DO-PadDOUT)") (class "Default")
      (node (ref "LED37") (pin "DOUT") (pinfunction "DO_DOUT") (pintype "output"))
    )
    (net (code "99") (name "unconnected-(MCU-BOOT0-Pad94)") (class "Default")
      (node (ref "MCU") (pin "94") (pinfunction "BOOT0_94") (pintype "bidirectional"))
    )
    (net (code "100") (name "unconnected-(MCU-PA0-WKUP-Pad22)") (class "Default")
      (node (ref "MCU") (pin "22") (pinfunction "PA0-WKUP_22") (pintype "bidirectional"))
    )
    (net (code "101") (name "unconnected-(MCU-PA2-Pad24)") (class "Default")
      (node (ref "MCU") (pin "24") (pinfunction "PA2_24") (pintype "bidirectional"))
    )
    (net (code "102") (name "unconnected-(MCU-PA3-Pad25)") (class "Default")
      (node (ref "MCU") (pin "25") (pinfunction "PA3_25") (pintype "bidirectional"))
    )
    (net (code "103") (name "unconnected-(MCU-PA4-Pad28)") (class "Default")
      (node (ref "MCU") (pin "28") (pinfunction "PA4_28") (pintype "bidirectional"))
    )
    (net (code "104") (name "unconnected-(MCU-PA5-Pad29)") (class "Default")
      (node (ref "MCU") (pin "29") (pinfunction "PA5_29") (pintype "bidirectional"))
    )
    (net (code "105") (name "unconnected-(MCU-PA6-Pad30)") (class "Default")
      (node (ref "MCU") (pin "30") (pinfunction "PA6_30") (pintype "bidirectional"))
    )
    (net (code "106") (name "unconnected-(MCU-PA7-Pad31)") (class "Default")
      (node (ref "MCU") (pin "31") (pinfunction "PA7_31") (pintype "bidirectional"))
    )
    (net (code "107") (name "unconnected-(MCU-PA8-Pad67)") (class "Default")
      (node (ref "MCU") (pin "67") (pinfunction "PA8_67") (pintype "bidirectional"))
    )
    (net (code "108") (name "unconnected-(MCU-PA9-Pad68)") (class "Default")
      (node (ref "MCU") (pin "68") (pinfunction "PA9_68") (pintype "bidirectional"))
    )
    (net (code "109") (name "unconnected-(MCU-PA10-Pad69)") (class "Default")
      (node (ref "MCU") (pin "69") (pinfunction "PA10_69") (pintype "bidirectional"))
    )
    (net (code "110") (name "unconnected-(MCU-PB0-Pad34)") (class "Default")
      (node (ref "MCU") (pin "34") (pinfunction "PB0_34") (pintype "bidirectional"))
    )
    (net (code "111") (name "unconnected-(MCU-PB1-Pad35)") (class "Default")
      (node (ref "MCU") (pin "35") (pinfunction "PB1_35") (pintype "bidirectional"))
    )
    (net (code "112") (name "unconnected-(MCU-PB2-Pad36)") (class "Default")
      (node (ref "MCU") (pin "36") (pinfunction "PB2_36") (pintype "bidirectional"))
    )
    (net (code "113") (name "unconnected-(MCU-PB5-Pad91)") (class "Default")
      (node (ref "MCU") (pin "91") (pinfunction "PB5_91") (pintype "bidirectional"))
    )
    (net (code "114") (name "unconnected-(MCU-PB6-Pad92)") (class "Default")
      (node (ref "MCU") (pin "92") (pinfunction "PB6_92") (pintype "bidirectional"))
    )
    (net (code "115") (name "unconnected-(MCU-PB7-Pad93)") (class "Default")
      (node (ref "MCU") (pin "93") (pinfunction "PB7_93") (pintype "bidirectional"))
    )
    (net (code "116") (name "unconnected-(MCU-PB8-Pad95)") (class "Default")
      (node (ref "MCU") (pin "95") (pinfunction "PB8_95") (pintype "bidirectional"))
    )
    (net (code "117") (name "unconnected-(MCU-PB9-Pad96)") (class "Default")
      (node (ref "MCU") (pin "96") (pinfunction "PB9_96") (pintype "bidirectional"))
    )
    (net (code "118") (name "unconnected-(MCU-PB10-Pad46)") (class "Default")
      (node (ref "MCU") (pin "46") (pinfunction "PB10_46") (pintype "bidirectional"))
    )
    (net (code "119") (name "unconnected-(MCU-PB11-Pad47)") (class "Default")
      (node (ref "MCU") (pin "47") (pinfunction "PB11_47") (pintype "bidirectional"))
    )
    (net (code "120") (name "unconnected-(MCU-PB12-Pad51)") (class "Default")
      (node (ref "MCU") (pin "51") (pinfunction "PB12_51") (pintype "bidirectional"))
    )
    (net (code "121") (name "unconnected-(MCU-PB13-Pad52)") (class "Default")
      (node (ref "MCU") (pin "52") (pinfunction "PB13_52") (pintype "bidirectional"))
    )
    (net (code "122") (name "unconnected-(MCU-PB14-Pad53)") (class "Default")
      (node (ref "MCU") (pin "53") (pinfunction "PB14_53") (pintype "bidirectional"))
    )
    (net (code "123") (name "unconnected-(MCU-PB15-Pad54)") (class "Default")
      (node (ref "MCU") (pin "54") (pinfunction "PB15_54") (pintype "bidirectional"))
    )
    (net (code "124") (name "unconnected-(MCU-PC0-Pad15)") (class "Default")
      (node (ref "MCU") (pin "15") (pinfunction "PC0_15") (pintype "bidirectional"))
    )
    (net (code "125") (name "unconnected-(MCU-PC1-Pad16)") (class "Default")
      (node (ref "MCU") (pin "16") (pinfunction "PC1_16") (pintype "bidirectional"))
    )
    (net (code "126") (name "unconnected-(MCU-PC2-Pad17)") (class "Default")
      (node (ref "MCU") (pin "17") (pinfunction "PC2_17") (pintype "bidirectional"))
    )
    (net (code "127") (name "unconnected-(MCU-PC3-Pad18)") (class "Default")
      (node (ref "MCU") (pin "18") (pinfunction "PC3_18") (pintype "bidirectional"))
    )
    (net (code "128") (name "unconnected-(MCU-PC4-Pad32)") (class "Default")
      (node (ref "MCU") (pin "32") (pinfunction "PC4_32") (pintype "bidirectional"))
    )
    (net (code "129") (name "unconnected-(MCU-PC5-Pad33)") (class "Default")
      (node (ref "MCU") (pin "33") (pinfunction "PC5_33") (pintype "bidirectional"))
    )
    (net (code "130") (name "unconnected-(MCU-PC6-Pad63)") (class "Default")
      (node (ref "MCU") (pin "63") (pinfunction "PC6_63") (pintype "bidirectional"))
    )
    (net (code "131") (name "unconnected-(MCU-PC7-Pad64)") (class "Default")
      (node (ref "MCU") (pin "64") (pinfunction "PC7_64") (pintype "bidirectional"))
    )
    (net (code "132") (name "unconnected-(MCU-PC8-Pad65)") (class "Default")
      (node (ref "MCU") (pin "65") (pinfunction "PC8_65") (pintype "bidirectional"))
    )
    (net (code "133") (name "unconnected-(MCU-PC9-Pad66)") (class "Default")
      (node (ref "MCU") (pin "66") (pinfunction "PC9_66") (pintype "bidirectional"))
    )
    (net (code "134") (name "unconnected-(MCU-PC10-Pad78)") (class "Default")
      (node (ref "MCU") (pin "78") (pinfunction "PC10_78") (pintype "bidirectional"))
    )
    (net (code "135") (name "unconnected-(MCU-PC11-Pad79)") (class "Default")
      (node (ref "MCU") (pin "79") (pinfunction "PC11_79") (pintype "bidirectional"))
    )
    (net (code "136") (name "unconnected-(MCU-PC12-Pad80)") (class "Default")
      (node (ref "MCU") (pin "80") (pinfunction "PC12_80") (pintype "bidirectional"))
    )
    (net (code "137") (name "unconnected-(MCU-PC13-Pad7)") (class "Default")
      (node (ref "MCU") (pin "7") (pinfunction "PC13_7") (pintype "bidirectional"))
    )
    (net (code "138") (name "unconnected-(MCU-PC14-Pad8)") (class "Default")
      (node (ref "MCU") (pin "8") (pinfunction "PC14_8") (pintype "bidirectional"))
    )
    (net (code "139") (name "unconnected-(MCU-PC15-Pad9)") (class "Default")
      (node (ref "MCU") (pin "9") (pinfunction "PC15_9") (pintype "bidirectional"))
    )
    (net (code "140") (name "unconnected-(MCU-PD0-Pad81)") (class "Default")
      (node (ref "MCU") (pin "81") (pinfunction "PD0_81") (pintype "bidirectional"))
    )
    (net (code "141") (name "unconnected-(MCU-PD1-Pad82)") (class "Default")
      (node (ref "MCU") (pin "82") (pinfunction "PD1_82") (pintype "bidirectional"))
    )
    (net (code "142") (name "unconnected-(MCU-PD2-Pad83)") (class "Default")
      (node (ref "MCU") (pin "83") (pinfunction "PD2_83") (pintype "bidirectional"))
    )
    (net (code "143") (name "unconnected-(MCU-PD3-Pad84)") (class "Default")
      (node (ref "MCU") (pin "84") (pinfunction "PD3_84") (pintype "bidirectional"))
    )
    (net (code "144") (name "unconnected-(MCU-PD4-Pad85)") (class "Default")
      (node (ref "MCU") (pin "85") (pinfunction "PD4_85") (pintype "bidirectional"))
    )
    (net (code "145") (name "unconnected-(MCU-PD5-Pad86)") (class "Default")
      (node (ref "MCU") (pin "86") (pinfunction "PD5_86") (pintype "bidirectional"))
    )
    (net (code "146") (name "unconnected-(MCU-PD6-Pad87)") (class "Default")
      (node (ref "MCU") (pin "87") (pinfunction "PD6_87") (pintype "bidirectional"))
    )
    (net (code "147") (name "unconnected-(MCU-PD7-Pad88)") (class "Default")
      (node (ref "MCU") (pin "88") (pinfunction "PD7_88") (pintype "bidirectional"))
    )
    (net (code "148") (name "unconnected-(MCU-PD8-Pad55)") (class "Default")
      (node (ref "MCU") (pin "55") (pinfunction "PD8_55") (pintype "bidirectional"))
    )
    (net (code "149") (name "unconnected-(MCU-PD9-Pad56)") (class "Default")
      (node (ref "MCU") (pin "56") (pinfunction "PD9_56") (pintype "bidirectional"))
    )
    (net (code "150") (name "unconnected-(MCU-PD10-Pad57)") (class "Default")
      (node (ref "MCU") (pin "57") (pinfunction "PD10_57") (pintype "bidirectional"))
    )
    (net (code "151") (name "unconnected-(MCU-PD11-Pad58)") (class "Default")
      (node (ref "MCU") (pin "58") (pinfunction "PD11_58") (pintype "bidirectional"))
    )
    (net (code "152") (name "unconnected-(MCU-PD12-Pad59)") (class "Default")
      (node (ref "MCU") (pin "59") (pinfunction "PD12_59") (pintype "bidirectional"))
    )
    (net (code "153") (name "unconnected-(MCU-PD13-Pad60)") (class "Default")
      (node (ref "MCU") (pin "60") (pinfunction "PD13_60") (pintype "bidirectional"))
    )
    (net (code "154") (name "unconnected-(MCU-PD14-Pad61)") (class "Default")
      (node (ref "MCU") (pin "61") (pinfunction "PD14_61") (pintype "bidirectional"))
    )
    (net (code "155") (name "unconnected-(MCU-PD15-Pad62)") (class "Default")
      (node (ref "MCU") (pin "62") (pinfunction "PD15_62") (pintype "bidirectional"))
    )
    (net (code "156") (name "unconnected-(MCU-PE0-Pad97)") (class "Default")
      (node (ref "MCU") (pin "97") (pinfunction "PE0_97") (pintype "bidirectional"))
    )
    (net (code "157") (name "unconnected-(MCU-PE1-Pad98)") (class "Default")
      (node (ref "MCU") (pin "98") (pinfunction "PE1_98") (pintype "bidirectional"))
    )
    (net (code "158") (name "unconnected-(MCU-PE2-Pad1)") (class "Default")
      (node (ref "MCU") (pin "1") (pinfunction "PE2_1") (pintype "bidirectional"))
    )
    (net (code "159") (name "unconnected-(MCU-PE3-Pad2)") (class "Default")
      (node (ref "MCU") (pin "2") (pinfunction "PE3_2") (pintype "bidirectional"))
    )
    (net (code "160") (name "unconnected-(MCU-PE4-Pad3)") (class "Default")
      (node (ref "MCU") (pin "3") (pinfunction "PE4_3") (pintype "bidirectional"))
    )
    (net (code "161") (name "unconnected-(MCU-PE5-Pad4)") (class "Default")
      (node (ref "MCU") (pin "4") (pinfunction "PE5_4") (pintype "bidirectional"))
    )
    (net (code "162") (name "unconnected-(MCU-PE6-Pad5)") (class "Default")
      (node (ref "MCU") (pin "5") (pinfunction "PE6_5") (pintype "bidirectional"))
    )
    (net (code "163") (name "unconnected-(MCU-PE7-Pad37)") (class "Default")
      (node (ref "MCU") (pin "37") (pinfunction "PE7_37") (pintype "bidirectional"))
    )
    (net (code "164") (name "unconnected-(MCU-PE8-Pad38)") (class "Default")
      (node (ref "MCU") (pin "38") (pinfunction "PE8_38") (pintype "bidirectional"))
    )
    (net (code "165") (name "unconnected-(MCU-PE10-Pad40)") (class "Default")
      (node (ref "MCU") (pin "40") (pinfunction "PE10_40") (pintype "bidirectional"))
    )
    (net (code "166") (name "unconnected-(MCU-PE12-Pad42)") (class "Default")
      (node (ref "MCU") (pin "42") (pinfunction "PE12_42") (pintype "bidirectional"))
    )
    (net (code "167") (name "unconnected-(MCU-PE13-Pad43)") (class "Default")
      (node (ref "MCU") (pin "43") (pinfunction "PE13_43") (pintype "bidirectional"))
    )
    (net (code "168") (name "unconnected-(MCU-PE14-Pad44)") (class "Default")
      (node (ref "MCU") (pin "44") (pinfunction "PE14_44") (pintype "bidirectional"))
    )
    (net (code "169") (name "unconnected-(MCU-PE15-Pad45)") (class "Default")
      (node (ref "MCU") (pin "45") (pinfunction "PE15_45") (pintype "bidirectional"))
    )
    (net (code "170") (name "unconnected-(PUSHPULL-1A-Pad2)") (class "Default")
      (node (ref "PUSHPULL") (pin "2") (pinfunction "1A_2") (pintype "bidirectional"))
    )
    (net (code "171") (name "unconnected-(PUSHPULL-2A-Pad5)") (class "Default")
      (node (ref "PUSHPULL") (pin "5") (pinfunction "2A_5") (pintype "bidirectional"))
    )
  )
)
